# io-board-f-d.net
KiCad netlist of a schematic drawn in EAGLE
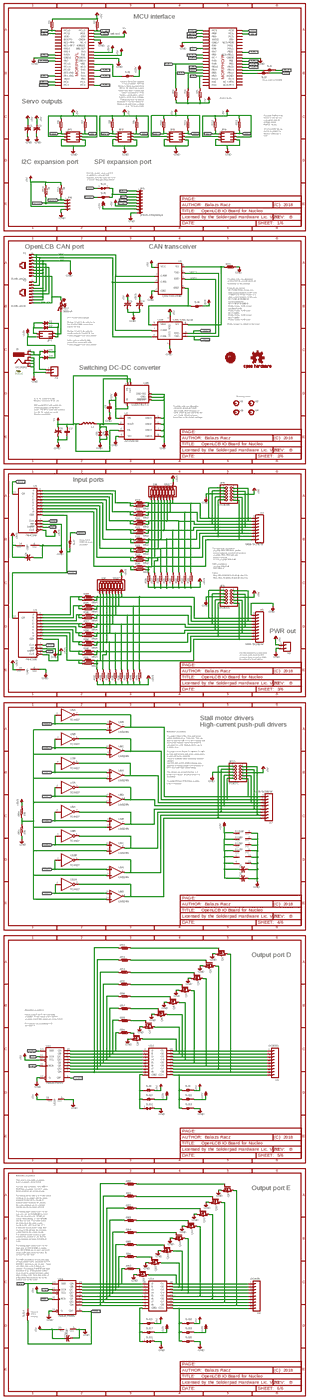
[diagram p0: schematic, sheet 1, overview]
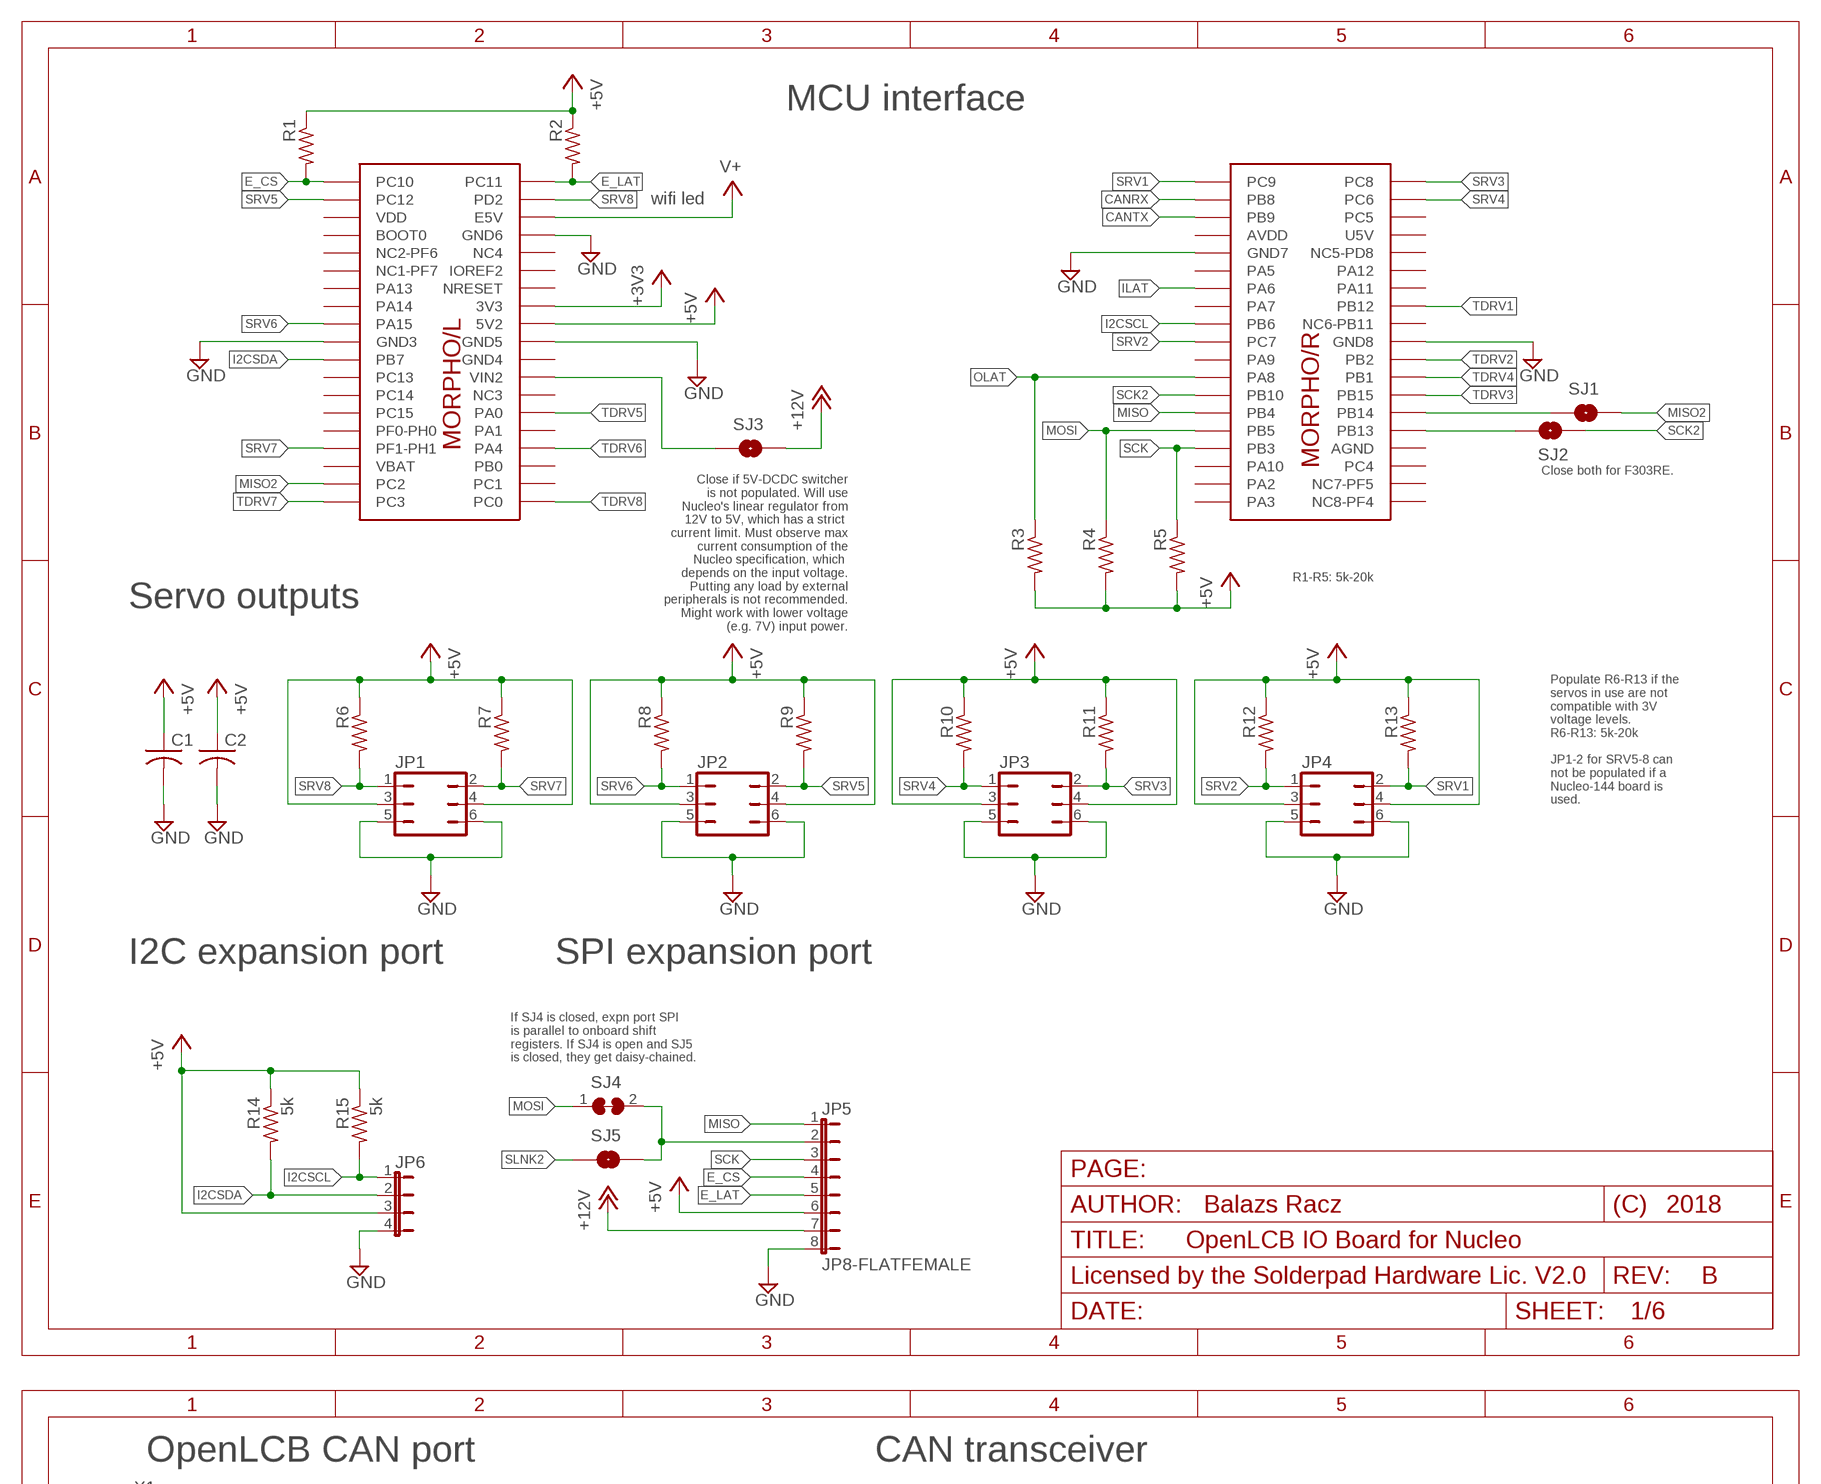
[diagram p1: schematic, sheet 1, part 1 of 4]
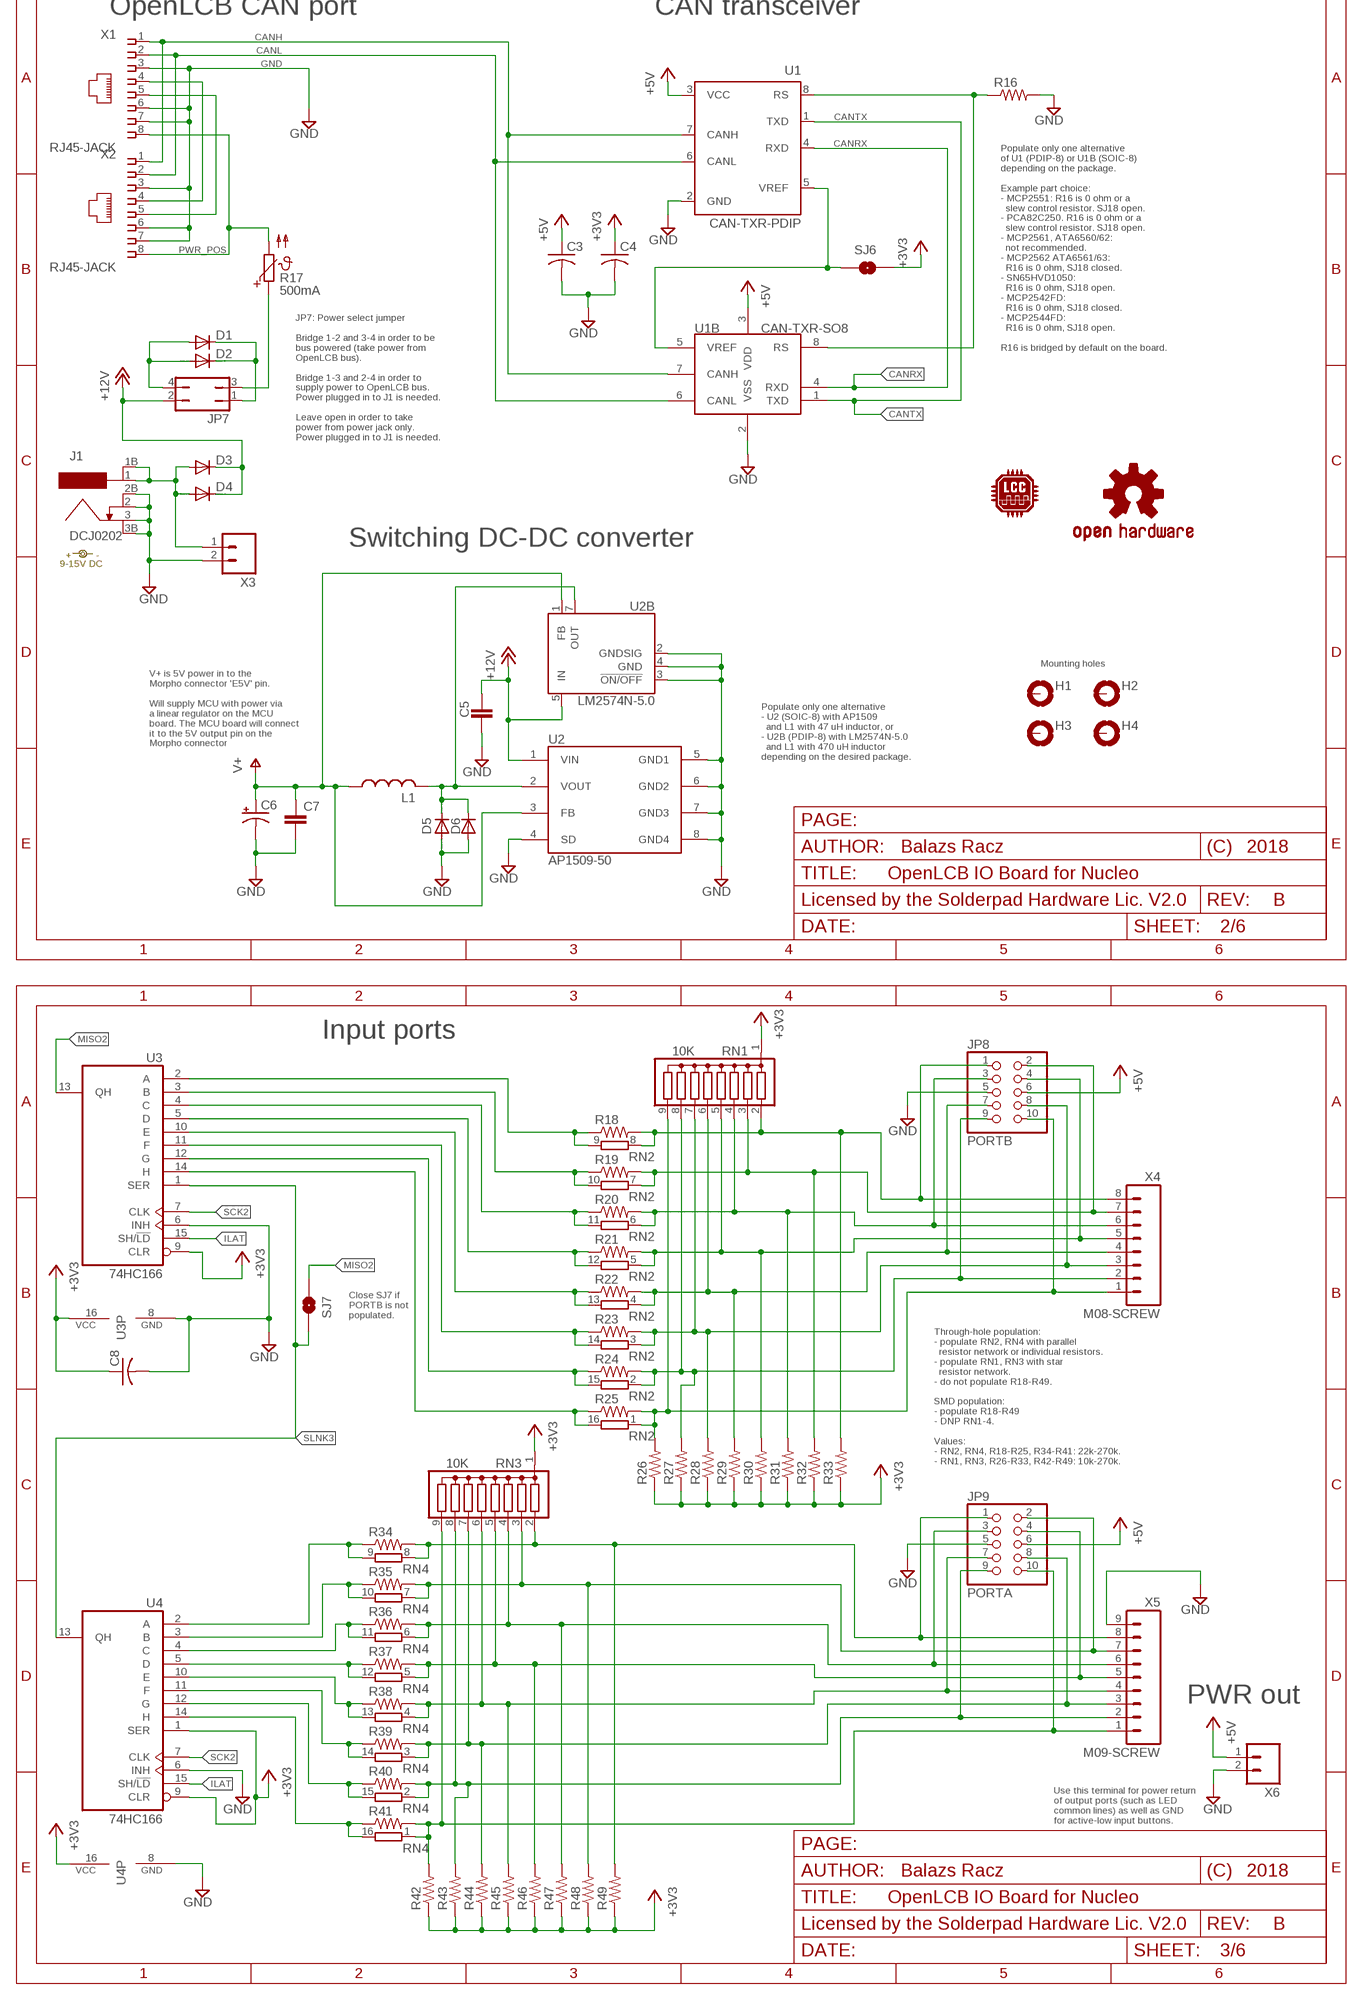
[diagram p2: schematic, sheet 1, part 2 of 4]
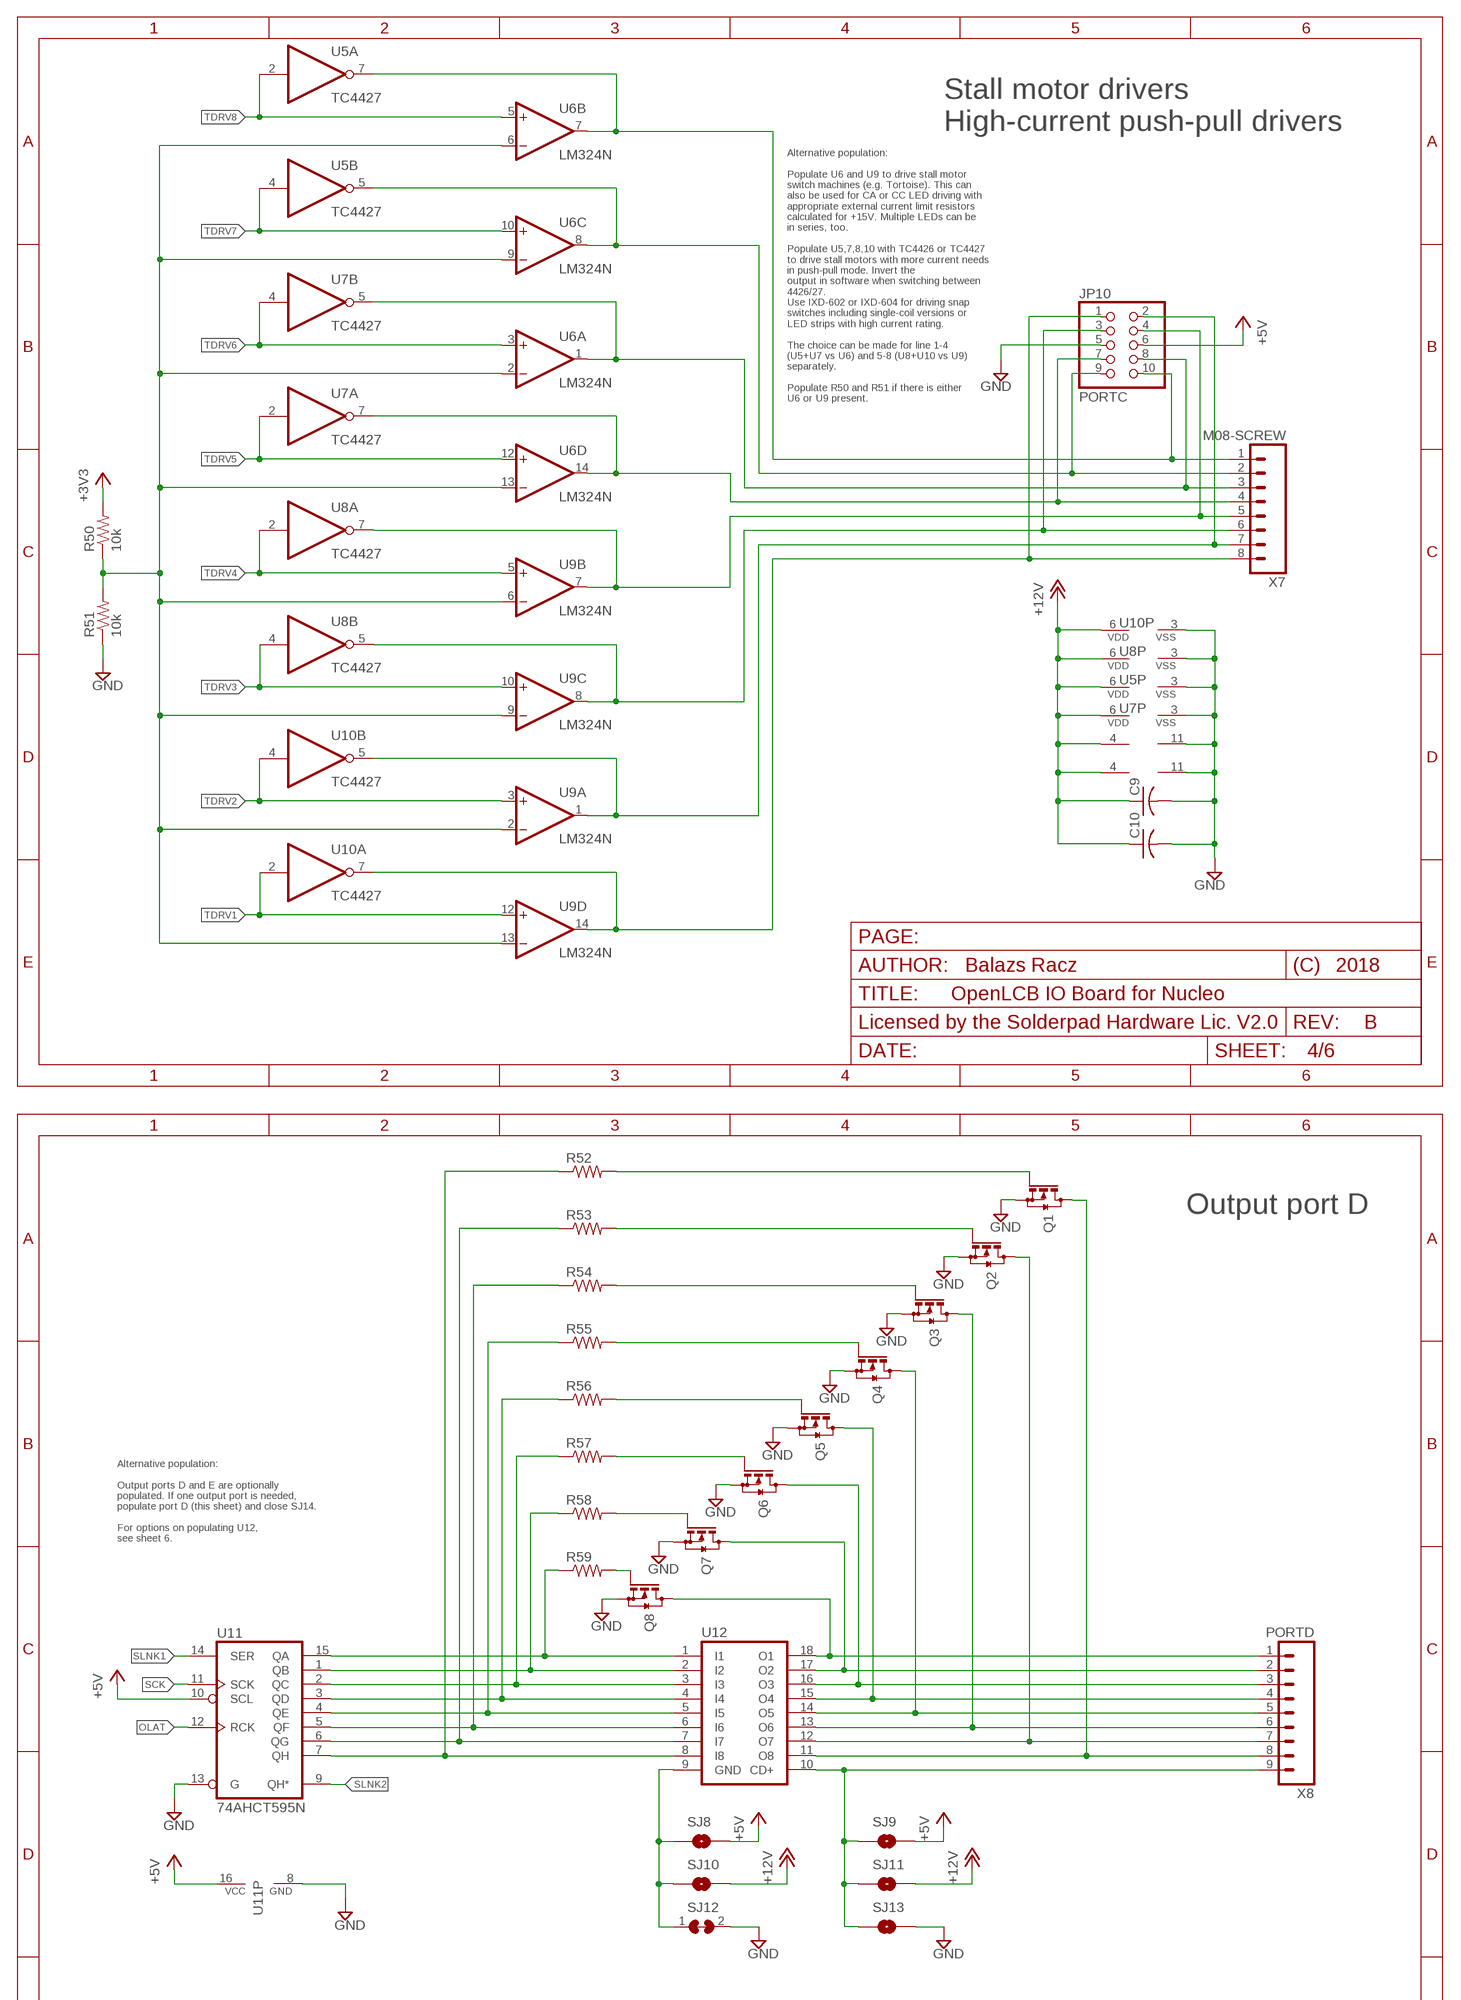
[diagram p3: schematic, sheet 1, part 3 of 4]
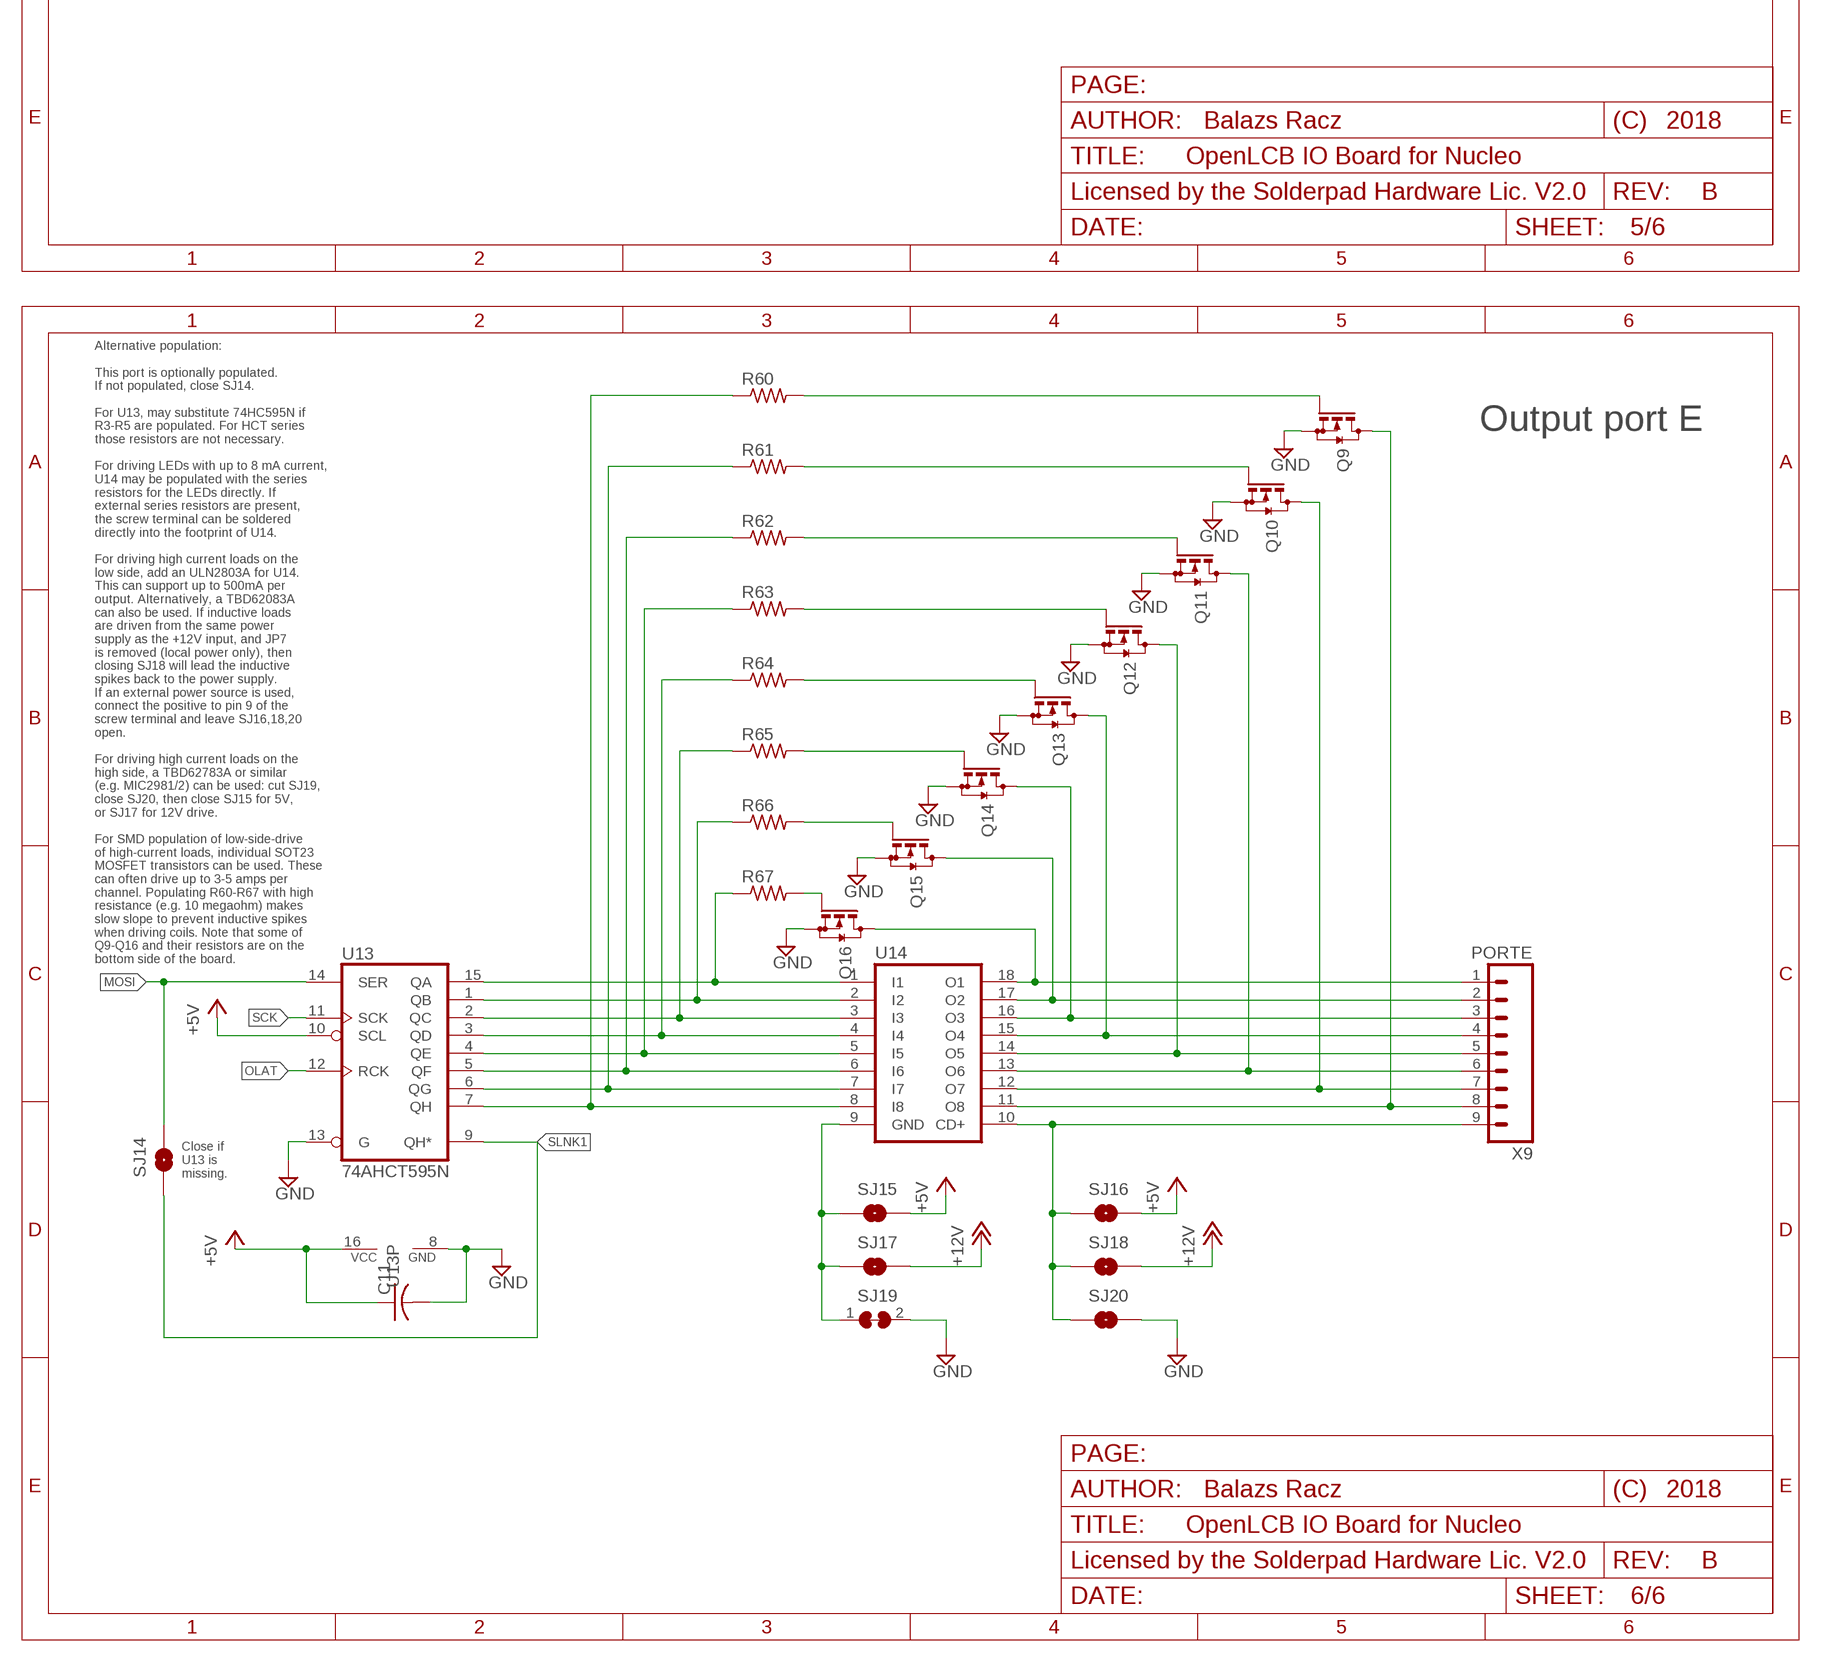
[diagram p4: schematic, sheet 1, part 4 of 4]

(export (version "E")
  (design (tool "Eeschema 10.0.6"))
  (components
    (comp (ref "C1")
      (value "C-USC1206")
      (footprint "eagle-import:C1206")
      (libsource (lib "eagle-import") (part "C-USC1206"))
    )
    (comp (ref "C2")
      (value "C-USC1206")
      (footprint "eagle-import:C1206")
      (libsource (lib "eagle-import") (part "C-USC1206"))
    )
    (comp (ref "C3")
      (value "C-USC0805")
      (footprint "eagle-import:C0805")
      (libsource (lib "eagle-import") (part "C-USC0805"))
    )
    (comp (ref "C4")
      (value "C-USC0805")
      (footprint "eagle-import:C0805")
      (libsource (lib "eagle-import") (part "C-USC0805"))
    )
    (comp (ref "C5")
      (value "C-EUC1206")
      (footprint "eagle-import:C1206")
      (libsource (lib "eagle-import") (part "C-EUC1206"))
    )
    (comp (ref "C6")
      (value "CPOL-USE2.5-5")
      (footprint "eagle-import:E2,5-5")
      (libsource (lib "eagle-import") (part "CPOL-USE2.5-5"))
    )
    (comp (ref "C7")
      (value "C-EUC1206")
      (footprint "eagle-import:C1206")
      (libsource (lib "eagle-import") (part "C-EUC1206"))
    )
    (comp (ref "C8")
      (value "C-USC0805")
      (footprint "eagle-import:C0805")
      (libsource (lib "eagle-import") (part "C-USC0805"))
    )
    (comp (ref "C9")
      (value "C-USC1206")
      (footprint "eagle-import:C1206")
      (libsource (lib "eagle-import") (part "C-USC1206"))
    )
    (comp (ref "C10")
      (value "C-USC1206")
      (footprint "eagle-import:C1206")
      (libsource (lib "eagle-import") (part "C-USC1206"))
    )
    (comp (ref "C11")
      (value "C-USC0805")
      (footprint "eagle-import:C0805")
      (libsource (lib "eagle-import") (part "C-USC0805"))
    )
    (comp (ref "D1")
      (value "DIODEDO-214AA-NODOC")
      (footprint "eagle-import:DO214AA-NODOC")
      (libsource (lib "eagle-import") (part "DIODEDO-214AA-NODOC"))
    )
    (comp (ref "D2")
      (value "DIODE-DO41-7.6")
      (footprint "eagle-import:DO41-7.6")
      (libsource (lib "eagle-import") (part "DIODE-DO41-7.6"))
    )
    (comp (ref "D3")
      (value "DIODEDO-214AA-NODOC")
      (footprint "eagle-import:DO214AA-NODOC")
      (libsource (lib "eagle-import") (part "DIODEDO-214AA-NODOC"))
    )
    (comp (ref "D4")
      (value "DIODE-DO41-7.6")
      (footprint "eagle-import:DO41-7.6")
      (libsource (lib "eagle-import") (part "DIODE-DO41-7.6"))
    )
    (comp (ref "D5")
      (value "DIODE-DO41-7.6")
      (footprint "eagle-import:DO41-7.6")
      (libsource (lib "eagle-import") (part "DIODE-DO41-7.6"))
    )
    (comp (ref "D6")
      (value "DIODEDO-214AA-NODOC")
      (footprint "eagle-import:DO214AA-NODOC")
      (libsource (lib "eagle-import") (part "DIODEDO-214AA-NODOC"))
    )
    (comp (ref "G1")
      (value "NUCLEO_64_GENERIC")
      (footprint "eagle-import:NUCLEO_BRD_BASE64")
      (libsource (lib "eagle-import") (part "NUCLEO_64_GENERIC"))
    )
    (comp (ref "H1")
      (value "MOUNT-PAD-ROUND3.3")
      (footprint "eagle-import:3,3-PAD")
      (libsource (lib "eagle-import") (part "MOUNT-PAD-ROUND3.3"))
    )
    (comp (ref "H2")
      (value "MOUNT-PAD-ROUND3.3")
      (footprint "eagle-import:3,3-PAD")
      (libsource (lib "eagle-import") (part "MOUNT-PAD-ROUND3.3"))
    )
    (comp (ref "H3")
      (value "MOUNT-PAD-ROUND3.3")
      (footprint "eagle-import:3,3-PAD")
      (libsource (lib "eagle-import") (part "MOUNT-PAD-ROUND3.3"))
    )
    (comp (ref "H4")
      (value "MOUNT-PAD-ROUND3.3")
      (footprint "eagle-import:3,3-PAD")
      (libsource (lib "eagle-import") (part "MOUNT-PAD-ROUND3.3"))
    )
    (comp (ref "J1")
      (value "DCJ0202")
      (footprint "eagle-import:DCJ0202")
      (libsource (lib "eagle-import") (part "DCJ0202"))
    )
    (comp (ref "JP1")
      (value "JP3Q")
      (footprint "eagle-import:JP3Q")
      (libsource (lib "eagle-import") (part "JP3Q"))
    )
    (comp (ref "JP2")
      (value "JP3Q")
      (footprint "eagle-import:JP3Q")
      (libsource (lib "eagle-import") (part "JP3Q"))
    )
    (comp (ref "JP3")
      (value "JP3Q")
      (footprint "eagle-import:JP3Q")
      (libsource (lib "eagle-import") (part "JP3Q"))
    )
    (comp (ref "JP4")
      (value "JP3Q")
      (footprint "eagle-import:JP3Q")
      (libsource (lib "eagle-import") (part "JP3Q"))
    )
    (comp (ref "JP5")
      (value "JP8-FLATFEMALE")
      (footprint "eagle-import:JP8F-FEM")
      (libsource (lib "eagle-import") (part "JP8-FLATFEMALE"))
    )
    (comp (ref "JP6")
      (value "JP4-FLAT")
      (footprint "eagle-import:JP4F")
      (libsource (lib "eagle-import") (part "JP4-FLAT"))
    )
    (comp (ref "JP7")
      (value "JP2Q")
      (footprint "eagle-import:JP2Q")
      (libsource (lib "eagle-import") (part "JP2Q"))
    )
    (comp (ref "JP8")
      (value "PORTB")
      (footprint "eagle-import:CON10M")
      (libsource (lib "eagle-import") (part "PINHD-2X5CN"))
    )
    (comp (ref "JP9")
      (value "PORTA")
      (footprint "eagle-import:CON10M")
      (libsource (lib "eagle-import") (part "PINHD-2X5CN"))
    )
    (comp (ref "JP10")
      (value "PORTC")
      (footprint "eagle-import:CON10M")
      (libsource (lib "eagle-import") (part "PINHD-2X5CN"))
    )
    (comp (ref "L1")
      (value "L-US")
      (footprint "eagle-import:L5-8,5")
      (libsource (lib "eagle-import") (part "L-US"))
    )
    (comp (ref "LG1")
      (value "LCC_LOGO")
      (footprint "eagle-import:LCC_LOGO")
      (libsource (lib "eagle-import") (part "LCC_LOGO"))
    )
    (comp (ref "LOGO1")
      (value "DOC-OSHW-LOGOM")
      (footprint "eagle-import:OSHW-LOGO-M")
      (libsource (lib "eagle-import") (part "DOC-OSHW-LOGOM"))
    )
    (comp (ref "P1")
      (value "9-15V DC")
      (footprint "eagle-import:POWER_USAGE")
      (libsource (lib "eagle-import") (part "DOC-POWER_LABEL"))
    )
    (comp (ref "Q1")
      (value "BSS123")
      (footprint "eagle-import:SOT23")
      (libsource (lib "eagle-import") (part "BSS123"))
    )
    (comp (ref "Q2")
      (value "BSS123")
      (footprint "eagle-import:SOT23")
      (libsource (lib "eagle-import") (part "BSS123"))
    )
    (comp (ref "Q3")
      (value "BSS123")
      (footprint "eagle-import:SOT23")
      (libsource (lib "eagle-import") (part "BSS123"))
    )
    (comp (ref "Q4")
      (value "BSS123")
      (footprint "eagle-import:SOT23")
      (libsource (lib "eagle-import") (part "BSS123"))
    )
    (comp (ref "Q5")
      (value "BSS123")
      (footprint "eagle-import:SOT23")
      (libsource (lib "eagle-import") (part "BSS123"))
    )
    (comp (ref "Q6")
      (value "BSS123")
      (footprint "eagle-import:SOT23")
      (libsource (lib "eagle-import") (part "BSS123"))
    )
    (comp (ref "Q7")
      (value "BSS123")
      (footprint "eagle-import:SOT23")
      (libsource (lib "eagle-import") (part "BSS123"))
    )
    (comp (ref "Q8")
      (value "BSS123")
      (footprint "eagle-import:SOT23")
      (libsource (lib "eagle-import") (part "BSS123"))
    )
    (comp (ref "Q9")
      (value "BSS123")
      (footprint "eagle-import:SOT23")
      (libsource (lib "eagle-import") (part "BSS123"))
    )
    (comp (ref "Q10")
      (value "BSS123")
      (footprint "eagle-import:SOT23")
      (libsource (lib "eagle-import") (part "BSS123"))
    )
    (comp (ref "Q11")
      (value "BSS123")
      (footprint "eagle-import:SOT23")
      (libsource (lib "eagle-import") (part "BSS123"))
    )
    (comp (ref "Q12")
      (value "BSS123")
      (footprint "eagle-import:SOT23")
      (libsource (lib "eagle-import") (part "BSS123"))
    )
    (comp (ref "Q13")
      (value "BSS123")
      (footprint "eagle-import:SOT23")
      (libsource (lib "eagle-import") (part "BSS123"))
    )
    (comp (ref "Q14")
      (value "BSS123")
      (footprint "eagle-import:SOT23")
      (libsource (lib "eagle-import") (part "BSS123"))
    )
    (comp (ref "Q15")
      (value "BSS123")
      (footprint "eagle-import:SOT23")
      (libsource (lib "eagle-import") (part "BSS123"))
    )
    (comp (ref "Q16")
      (value "BSS123")
      (footprint "eagle-import:SOT23")
      (libsource (lib "eagle-import") (part "BSS123"))
    )
    (comp (ref "R1")
      (value "R-US_R0805")
      (footprint "eagle-import:R0805")
      (libsource (lib "eagle-import") (part "rcl_334_R-US_R0805"))
    )
    (comp (ref "R2")
      (value "R-US_R0805")
      (footprint "eagle-import:R0805")
      (libsource (lib "eagle-import") (part "rcl_334_R-US_R0805"))
    )
    (comp (ref "R3")
      (value "R-US_R0805")
      (footprint "eagle-import:R0805")
      (libsource (lib "eagle-import") (part "rcl_334_R-US_R0805"))
    )
    (comp (ref "R4")
      (value "R-US_R0805")
      (footprint "eagle-import:R0805")
      (libsource (lib "eagle-import") (part "rcl_334_R-US_R0805"))
    )
    (comp (ref "R5")
      (value "R-US_R0805")
      (footprint "eagle-import:R0805")
      (libsource (lib "eagle-import") (part "rcl_334_R-US_R0805"))
    )
    (comp (ref "R6")
      (value "R-US_R0805")
      (footprint "eagle-import:R0805")
      (libsource (lib "eagle-import") (part "rcl_334_R-US_R0805"))
    )
    (comp (ref "R7")
      (value "R-US_R0805")
      (footprint "eagle-import:R0805")
      (libsource (lib "eagle-import") (part "rcl_334_R-US_R0805"))
    )
    (comp (ref "R8")
      (value "R-US_R0805")
      (footprint "eagle-import:R0805")
      (libsource (lib "eagle-import") (part "rcl_334_R-US_R0805"))
    )
    (comp (ref "R9")
      (value "R-US_R0805")
      (footprint "eagle-import:R0805")
      (libsource (lib "eagle-import") (part "rcl_334_R-US_R0805"))
    )
    (comp (ref "R10")
      (value "R-US_R0805")
      (footprint "eagle-import:R0805")
      (libsource (lib "eagle-import") (part "rcl_334_R-US_R0805"))
    )
    (comp (ref "R11")
      (value "R-US_R0805")
      (footprint "eagle-import:R0805")
      (libsource (lib "eagle-import") (part "rcl_334_R-US_R0805"))
    )
    (comp (ref "R12")
      (value "R-US_R0805")
      (footprint "eagle-import:R0805")
      (libsource (lib "eagle-import") (part "rcl_334_R-US_R0805"))
    )
    (comp (ref "R13")
      (value "R-US_R0805")
      (footprint "eagle-import:R0805")
      (libsource (lib "eagle-import") (part "rcl_334_R-US_R0805"))
    )
    (comp (ref "R14")
      (value "5k")
      (footprint "eagle-import:R0805")
      (libsource (lib "eagle-import") (part "rcl_334_R-US_R0805"))
    )
    (comp (ref "R15")
      (value "5k")
      (footprint "eagle-import:R0805")
      (libsource (lib "eagle-import") (part "rcl_334_R-US_R0805"))
    )
    (comp (ref "R16")
      (value "R-US_R0805")
      (footprint "eagle-import:R0805")
      (libsource (lib "eagle-import") (part "rcl_334_R-US_R0805"))
    )
    (comp (ref "R17")
      (value "500mA")
      (footprint "eagle-import:PTC1812")
      (libsource (lib "eagle-import") (part "PTC_1812"))
    )
    (comp (ref "R18")
      (value "R-US_R0603")
      (footprint "eagle-import:R0603")
      (libsource (lib "eagle-import") (part "rcl_334_R-US_R0603"))
    )
    (comp (ref "R19")
      (value "R-US_R0603")
      (footprint "eagle-import:R0603")
      (libsource (lib "eagle-import") (part "rcl_334_R-US_R0603"))
    )
    (comp (ref "R20")
      (value "R-US_R0603")
      (footprint "eagle-import:R0603")
      (libsource (lib "eagle-import") (part "rcl_334_R-US_R0603"))
    )
    (comp (ref "R21")
      (value "R-US_R0603")
      (footprint "eagle-import:R0603")
      (libsource (lib "eagle-import") (part "rcl_334_R-US_R0603"))
    )
    (comp (ref "R22")
      (value "R-US_R0603")
      (footprint "eagle-import:R0603")
      (libsource (lib "eagle-import") (part "rcl_334_R-US_R0603"))
    )
    (comp (ref "R23")
      (value "R-US_R0603")
      (footprint "eagle-import:R0603")
      (libsource (lib "eagle-import") (part "rcl_334_R-US_R0603"))
    )
    (comp (ref "R24")
      (value "R-US_R0603")
      (footprint "eagle-import:R0603")
      (libsource (lib "eagle-import") (part "rcl_334_R-US_R0603"))
    )
    (comp (ref "R25")
      (value "R-US_R0603")
      (footprint "eagle-import:R0603")
      (libsource (lib "eagle-import") (part "rcl_334_R-US_R0603"))
    )
    (comp (ref "R26")
      (value "R-US")
      (footprint "eagle-import:R0603")
      (libsource (lib "eagle-import") (part "R-US"))
    )
    (comp (ref "R27")
      (value "R-US")
      (footprint "eagle-import:R0603")
      (libsource (lib "eagle-import") (part "R-US"))
    )
    (comp (ref "R28")
      (value "R-US")
      (footprint "eagle-import:R0603")
      (libsource (lib "eagle-import") (part "R-US"))
    )
    (comp (ref "R29")
      (value "R-US")
      (footprint "eagle-import:R0603")
      (libsource (lib "eagle-import") (part "R-US"))
    )
    (comp (ref "R30")
      (value "R-US")
      (footprint "eagle-import:R0603")
      (libsource (lib "eagle-import") (part "R-US"))
    )
    (comp (ref "R31")
      (value "R-US")
      (footprint "eagle-import:R0603")
      (libsource (lib "eagle-import") (part "R-US"))
    )
    (comp (ref "R32")
      (value "R-US")
      (footprint "eagle-import:R0603")
      (libsource (lib "eagle-import") (part "R-US"))
    )
    (comp (ref "R33")
      (value "R-US")
      (footprint "eagle-import:R0603")
      (libsource (lib "eagle-import") (part "R-US"))
    )
    (comp (ref "R34")
      (value "R-US_R0603")
      (footprint "eagle-import:R0603")
      (libsource (lib "eagle-import") (part "rcl_334_R-US_R0603"))
    )
    (comp (ref "R35")
      (value "R-US_R0603")
      (footprint "eagle-import:R0603")
      (libsource (lib "eagle-import") (part "rcl_334_R-US_R0603"))
    )
    (comp (ref "R36")
      (value "R-US_R0603")
      (footprint "eagle-import:R0603")
      (libsource (lib "eagle-import") (part "rcl_334_R-US_R0603"))
    )
    (comp (ref "R37")
      (value "R-US_R0603")
      (footprint "eagle-import:R0603")
      (libsource (lib "eagle-import") (part "rcl_334_R-US_R0603"))
    )
    (comp (ref "R38")
      (value "R-US_R0603")
      (footprint "eagle-import:R0603")
      (libsource (lib "eagle-import") (part "rcl_334_R-US_R0603"))
    )
    (comp (ref "R39")
      (value "R-US_R0603")
      (footprint "eagle-import:R0603")
      (libsource (lib "eagle-import") (part "rcl_334_R-US_R0603"))
    )
    (comp (ref "R40")
      (value "R-US_R0603")
      (footprint "eagle-import:R0603")
      (libsource (lib "eagle-import") (part "rcl_334_R-US_R0603"))
    )
    (comp (ref "R41")
      (value "R-US_R0603")
      (footprint "eagle-import:R0603")
      (libsource (lib "eagle-import") (part "rcl_334_R-US_R0603"))
    )
    (comp (ref "R42")
      (value "R-US")
      (footprint "eagle-import:R0603")
      (libsource (lib "eagle-import") (part "R-US"))
    )
    (comp (ref "R43")
      (value "R-US")
      (footprint "eagle-import:R0603")
      (libsource (lib "eagle-import") (part "R-US"))
    )
    (comp (ref "R44")
      (value "R-US")
      (footprint "eagle-import:R0603")
      (libsource (lib "eagle-import") (part "R-US"))
    )
    (comp (ref "R45")
      (value "R-US")
      (footprint "eagle-import:R0603")
      (libsource (lib "eagle-import") (part "R-US"))
    )
    (comp (ref "R46")
      (value "R-US")
      (footprint "eagle-import:R0603")
      (libsource (lib "eagle-import") (part "R-US"))
    )
    (comp (ref "R47")
      (value "R-US")
      (footprint "eagle-import:R0603")
      (libsource (lib "eagle-import") (part "R-US"))
    )
    (comp (ref "R48")
      (value "R-US")
      (footprint "eagle-import:R0603")
      (libsource (lib "eagle-import") (part "R-US"))
    )
    (comp (ref "R49")
      (value "R-US")
      (footprint "eagle-import:R0603")
      (libsource (lib "eagle-import") (part "R-US"))
    )
    (comp (ref "R50")
      (value "10k")
      (footprint "eagle-import:R0805")
      (libsource (lib "eagle-import") (part "R-US_R0805"))
    )
    (comp (ref "R51")
      (value "10k")
      (footprint "eagle-import:R0805")
      (libsource (lib "eagle-import") (part "R-US_R0805"))
    )
    (comp (ref "R52")
      (value "R-US_R0603")
      (footprint "eagle-import:R0603")
      (libsource (lib "eagle-import") (part "R-US_R0603"))
    )
    (comp (ref "R53")
      (value "R-US_R0603")
      (footprint "eagle-import:R0603")
      (libsource (lib "eagle-import") (part "R-US_R0603"))
    )
    (comp (ref "R54")
      (value "R-US_R0603")
      (footprint "eagle-import:R0603")
      (libsource (lib "eagle-import") (part "R-US_R0603"))
    )
    (comp (ref "R55")
      (value "R-US_R0603")
      (footprint "eagle-import:R0603")
      (libsource (lib "eagle-import") (part "R-US_R0603"))
    )
    (comp (ref "R56")
      (value "R-US_R0603")
      (footprint "eagle-import:R0603")
      (libsource (lib "eagle-import") (part "R-US_R0603"))
    )
    (comp (ref "R57")
      (value "R-US_R0603")
      (footprint "eagle-import:R0603")
      (libsource (lib "eagle-import") (part "R-US_R0603"))
    )
    (comp (ref "R58")
      (value "R-US_R0603")
      (footprint "eagle-import:R0603")
      (libsource (lib "eagle-import") (part "R-US_R0603"))
    )
    (comp (ref "R59")
      (value "R-US_R0603")
      (footprint "eagle-import:R0603")
      (libsource (lib "eagle-import") (part "R-US_R0603"))
    )
    (comp (ref "R60")
      (value "R-US_R0603")
      (footprint "eagle-import:R0603")
      (libsource (lib "eagle-import") (part "R-US_R0603"))
    )
    (comp (ref "R61")
      (value "R-US_R0603")
      (footprint "eagle-import:R0603")
      (libsource (lib "eagle-import") (part "R-US_R0603"))
    )
    (comp (ref "R62")
      (value "R-US_R0603")
      (footprint "eagle-import:R0603")
      (libsource (lib "eagle-import") (part "R-US_R0603"))
    )
    (comp (ref "R63")
      (value "R-US_R0603")
      (footprint "eagle-import:R0603")
      (libsource (lib "eagle-import") (part "R-US_R0603"))
    )
    (comp (ref "R64")
      (value "R-US_R0603")
      (footprint "eagle-import:R0603")
      (libsource (lib "eagle-import") (part "R-US_R0603"))
    )
    (comp (ref "R65")
      (value "R-US_R0603")
      (footprint "eagle-import:R0603")
      (libsource (lib "eagle-import") (part "R-US_R0603"))
    )
    (comp (ref "R66")
      (value "R-US_R0603")
      (footprint "eagle-import:R0603")
      (libsource (lib "eagle-import") (part "R-US_R0603"))
    )
    (comp (ref "R67")
      (value "R-US_R0603")
      (footprint "eagle-import:R0603")
      (libsource (lib "eagle-import") (part "R-US_R0603"))
    )
    (comp (ref "RN1")
      (value "10K")
      (footprint "eagle-import:SIL9")
      (libsource (lib "eagle-import") (part "G08R"))
    )
    (comp (ref "RN2")
      (value "8R-P")
      (footprint "eagle-import:DIL16")
      (libsource (lib "eagle-import") (part "8R-P"))
    )
    (comp (ref "RN3")
      (value "10K")
      (footprint "eagle-import:SIL9")
      (libsource (lib "eagle-import") (part "G08R"))
    )
    (comp (ref "RN4")
      (value "8R-P")
      (footprint "eagle-import:DIL16")
      (libsource (lib "eagle-import") (part "8R-P"))
    )
    (comp (ref "SJ1")
      (value "SJRND2")
      (footprint "eagle-import:SJ_RND2")
      (libsource (lib "eagle-import") (part "SJRND2"))
    )
    (comp (ref "SJ2")
      (value "SJRND2")
      (footprint "eagle-import:SJ_RND2")
      (libsource (lib "eagle-import") (part "SJRND2"))
    )
    (comp (ref "SJ3")
      (value "SJRND2")
      (footprint "eagle-import:SJ_RND2")
      (libsource (lib "eagle-import") (part "SJRND2"))
    )
    (comp (ref "SJ4")
      (value "SJ-C")
      (footprint "eagle-import:SJW-C")
      (libsource (lib "eagle-import") (part "SJ-C"))
    )
    (comp (ref "SJ5")
      (value "SJRND2")
      (footprint "eagle-import:SJ_RND2")
      (libsource (lib "eagle-import") (part "SJRND2"))
    )
    (comp (ref "SJ6")
      (value "SJRND2")
      (footprint "eagle-import:SJ_RND2")
      (libsource (lib "eagle-import") (part "SJRND2"))
    )
    (comp (ref "SJ7")
      (value "SJRND2")
      (footprint "eagle-import:SJ_RND2")
      (libsource (lib "eagle-import") (part "SJRND2"))
    )
    (comp (ref "SJ8")
      (value "SJRND2")
      (footprint "eagle-import:SJ_RND2")
      (libsource (lib "eagle-import") (part "SJRND2"))
    )
    (comp (ref "SJ9")
      (value "SJRND2")
      (footprint "eagle-import:SJ_RND2")
      (libsource (lib "eagle-import") (part "SJRND2"))
    )
    (comp (ref "SJ10")
      (value "SJRND2")
      (footprint "eagle-import:SJ_RND2")
      (libsource (lib "eagle-import") (part "SJRND2"))
    )
    (comp (ref "SJ11")
      (value "SJRND2")
      (footprint "eagle-import:SJ_RND2")
      (libsource (lib "eagle-import") (part "SJRND2"))
    )
    (comp (ref "SJ12")
      (value "SJ-C")
      (footprint "eagle-import:SJW-C")
      (libsource (lib "eagle-import") (part "SJ-C"))
    )
    (comp (ref "SJ13")
      (value "SJRND2")
      (footprint "eagle-import:SJ_RND2")
      (libsource (lib "eagle-import") (part "SJRND2"))
    )
    (comp (ref "SJ14")
      (value "SJRND2")
      (footprint "eagle-import:SJ_RND2")
      (libsource (lib "eagle-import") (part "SJRND2"))
    )
    (comp (ref "SJ15")
      (value "SJRND2")
      (footprint "eagle-import:SJ_RND2")
      (libsource (lib "eagle-import") (part "SJRND2"))
    )
    (comp (ref "SJ16")
      (value "SJRND2")
      (footprint "eagle-import:SJ_RND2")
      (libsource (lib "eagle-import") (part "SJRND2"))
    )
    (comp (ref "SJ17")
      (value "SJRND2")
      (footprint "eagle-import:SJ_RND2")
      (libsource (lib "eagle-import") (part "SJRND2"))
    )
    (comp (ref "SJ18")
      (value "SJRND2")
      (footprint "eagle-import:SJ_RND2")
      (libsource (lib "eagle-import") (part "SJRND2"))
    )
    (comp (ref "SJ19")
      (value "SJ-C")
      (footprint "eagle-import:SJW-C")
      (libsource (lib "eagle-import") (part "SJ-C"))
    )
    (comp (ref "SJ20")
      (value "SJRND2")
      (footprint "eagle-import:SJ_RND2")
      (libsource (lib "eagle-import") (part "SJRND2"))
    )
    (comp (ref "U1")
      (value "CAN-TXR-PDIP")
      (footprint "eagle-import:DIL08")
      (libsource (lib "eagle-import") (part "PCA82C250"))
    )
    (comp (ref "U1B")
      (value "CAN-TXR-SO8")
      (footprint "eagle-import:SO-08")
      (libsource (lib "eagle-import") (part "MCP2551-SN"))
    )
    (comp (ref "U2")
      (value "AP1509-50")
      (footprint "eagle-import:SO-08")
      (libsource (lib "eagle-import") (part "AP1509"))
    )
    (comp (ref "U2B")
      (value "LM2574N-5.0")
      (footprint "eagle-import:DIL08")
      (libsource (lib "eagle-import") (part "LM2574?-N5.0"))
    )
    (comp (ref "U3")
      (value "74HC166")
      (footprint "eagle-import:DIL16")
      (libsource (lib "eagle-import") (part "74166N"))
    )
    (comp (ref "U4")
      (value "74HC166")
      (footprint "eagle-import:DIL16")
      (libsource (lib "eagle-import") (part "74166N"))
    )
    (comp (ref "U5")
      (value "TC4427")
      (footprint "eagle-import:DIL08-LONG")
      (libsource (lib "eagle-import") (part "TC4426APDIP"))
    )
    (comp (ref "U6")
      (value "LM324N")
      (footprint "eagle-import:DIL14")
      (libsource (lib "eagle-import") (part "LM324N"))
    )
    (comp (ref "U7")
      (value "TC4427")
      (footprint "eagle-import:DIL08-LONG")
      (libsource (lib "eagle-import") (part "TC4426APDIP"))
    )
    (comp (ref "U8")
      (value "TC4427")
      (footprint "eagle-import:DIL08-LONG")
      (libsource (lib "eagle-import") (part "TC4426APDIP"))
    )
    (comp (ref "U9")
      (value "LM324N")
      (footprint "eagle-import:DIL14")
      (libsource (lib "eagle-import") (part "LM324N"))
    )
    (comp (ref "U10")
      (value "TC4427")
      (footprint "eagle-import:DIL08-LONG")
      (libsource (lib "eagle-import") (part "TC4426APDIP"))
    )
    (comp (ref "U11")
      (value "74AHCT595N")
      (footprint "eagle-import:DIL16")
      (libsource (lib "eagle-import") (part "74595NHCT"))
    )
    (comp (ref "U12")
      (value "ULN2803A")
      (footprint "eagle-import:DIL18-THIN")
      (libsource (lib "eagle-import") (part "ULN2803A"))
    )
    (comp (ref "U13")
      (value "74AHCT595N")
      (footprint "eagle-import:DIL16")
      (libsource (lib "eagle-import") (part "74595NHCT"))
    )
    (comp (ref "U14")
      (value "ULN2803A")
      (footprint "eagle-import:DIL18-THIN")
      (libsource (lib "eagle-import") (part "ULN2803A"))
    )
    (comp (ref "X1")
      (value "RJ45-JACK")
      (footprint "eagle-import:RJ45-PULSE-E5J88")
      (libsource (lib "eagle-import") (part "RJ45-JACKRJ45-PULSE-E5J00"))
    )
    (comp (ref "X2")
      (value "RJ45-JACK")
      (footprint "eagle-import:RJ45-PULSE-E5J88")
      (libsource (lib "eagle-import") (part "RJ45-JACKRJ45-PULSE-E5J00"))
    )
    (comp (ref "X3")
      (value "CONNECTOR-M023.5MM-LOCK")
      (footprint "eagle-import:SCREWTERMINAL-3.5MM-2_LOCK")
      (libsource (lib "eagle-import") (part "CONNECTOR-M023.5MM-LOCK"))
    )
    (comp (ref "X4")
      (value "M08-SCREW")
      (footprint "eagle-import:1X08_TERMINAL")
      (libsource (lib "eagle-import") (part "M08-SCREW"))
    )
    (comp (ref "X5")
      (value "M09-SCREW")
      (footprint "eagle-import:1X09_TERMINAL")
      (libsource (lib "eagle-import") (part "M09-SCREW"))
    )
    (comp (ref "X6")
      (value "CONNECTOR-M023.5MM-LOCK")
      (footprint "eagle-import:SCREWTERMINAL-3.5MM-2_LOCK")
      (libsource (lib "eagle-import") (part "CONNECTOR-M023.5MM-LOCK"))
    )
    (comp (ref "X7")
      (value "M08-SCREW")
      (footprint "eagle-import:1X08_TERMINAL")
      (libsource (lib "eagle-import") (part "M08-SCREW"))
    )
    (comp (ref "X8")
      (value "PORTD")
      (footprint "eagle-import:1X09_TERMINAL")
      (libsource (lib "eagle-import") (part "M09-SCREW"))
    )
    (comp (ref "X9")
      (value "PORTE")
      (footprint "eagle-import:1X09_TERMINAL")
      (libsource (lib "eagle-import") (part "M09-SCREW"))
    )
  )
  (nets
    (net (code "1") (name "+3V3") (class "Default")
      (node (ref "C4") (pin "1") (pinfunction "1_1") (pintype "passive"))
      (node (ref "C8") (pin "1") (pinfunction "1_1") (pintype "passive"))
      (node (ref "G1") (pin "3V3") (pinfunction "3V3_3V3") (pintype "power_in"))
      (node (ref "R26") (pin "1") (pinfunction "1_1") (pintype "passive"))
      (node (ref "R27") (pin "1") (pinfunction "1_1") (pintype "passive"))
      (node (ref "R28") (pin "1") (pinfunction "1_1") (pintype "passive"))
      (node (ref "R29") (pin "1") (pinfunction "1_1") (pintype "passive"))
      (node (ref "R30") (pin "1") (pinfunction "1_1") (pintype "passive"))
      (node (ref "R31") (pin "1") (pinfunction "1_1") (pintype "passive"))
      (node (ref "R32") (pin "1") (pinfunction "1_1") (pintype "passive"))
      (node (ref "R33") (pin "1") (pinfunction "1_1") (pintype "passive"))
      (node (ref "R42") (pin "1") (pinfunction "1_1") (pintype "passive"))
      (node (ref "R43") (pin "1") (pinfunction "1_1") (pintype "passive"))
      (node (ref "R44") (pin "1") (pinfunction "1_1") (pintype "passive"))
      (node (ref "R45") (pin "1") (pinfunction "1_1") (pintype "passive"))
      (node (ref "R46") (pin "1") (pinfunction "1_1") (pintype "passive"))
      (node (ref "R47") (pin "1") (pinfunction "1_1") (pintype "passive"))
      (node (ref "R48") (pin "1") (pinfunction "1_1") (pintype "passive"))
      (node (ref "R49") (pin "1") (pinfunction "1_1") (pintype "passive"))
      (node (ref "R50") (pin "2") (pinfunction "2_2") (pintype "passive"))
      (node (ref "RN1") (pin "1") (pinfunction "1_1") (pintype "passive"))
      (node (ref "RN3") (pin "1") (pinfunction "1_1") (pintype "passive"))
      (node (ref "SJ6") (pin "P$2") (pinfunction "2_P$2") (pintype "passive"))
      (node (ref "U3") (pin "16") (pinfunction "VCC_16") (pintype "power_in"))
      (node (ref "U3") (pin "9") (pinfunction "CLR_9") (pintype "input"))
      (node (ref "U4") (pin "1") (pinfunction "SER_1") (pintype "input"))
      (node (ref "U4") (pin "16") (pinfunction "VCC_16") (pintype "power_in"))
      (node (ref "U4") (pin "9") (pinfunction "CLR_9") (pintype "input"))
    )
    (net (code "2") (name "+5V") (class "Default")
      (node (ref "C1") (pin "1") (pinfunction "1_1") (pintype "passive"))
      (node (ref "C11") (pin "1") (pinfunction "1_1") (pintype "passive"))
      (node (ref "C2") (pin "1") (pinfunction "1_1") (pintype "passive"))
      (node (ref "C3") (pin "1") (pinfunction "1_1") (pintype "passive"))
      (node (ref "G1") (pin "5V2") (pinfunction "5V2_5V2") (pintype "power_in"))
      (node (ref "JP1") (pin "3") (pinfunction "3_3") (pintype "passive"))
      (node (ref "JP1") (pin "4") (pinfunction "4_4") (pintype "passive"))
      (node (ref "JP10") (pin "6") (pinfunction "6_6") (pintype "passive"))
      (node (ref "JP2") (pin "3") (pinfunction "3_3") (pintype "passive"))
      (node (ref "JP2") (pin "4") (pinfunction "4_4") (pintype "passive"))
      (node (ref "JP3") (pin "3") (pinfunction "3_3") (pintype "passive"))
      (node (ref "JP3") (pin "4") (pinfunction "4_4") (pintype "passive"))
      (node (ref "JP4") (pin "3") (pinfunction "3_3") (pintype "passive"))
      (node (ref "JP4") (pin "4") (pinfunction "4_4") (pintype "passive"))
      (node (ref "JP5") (pin "6") (pinfunction "6_6") (pintype "passive"))
      (node (ref "JP6") (pin "3") (pinfunction "3_3") (pintype "passive"))
      (node (ref "JP8") (pin "6") (pinfunction "6_6") (pintype "passive"))
      (node (ref "JP9") (pin "6") (pinfunction "6_6") (pintype "passive"))
      (node (ref "R1") (pin "1") (pinfunction "1_1") (pintype "passive"))
      (node (ref "R10") (pin "1") (pinfunction "1_1") (pintype "passive"))
      (node (ref "R11") (pin "1") (pinfunction "1_1") (pintype "passive"))
      (node (ref "R12") (pin "1") (pinfunction "1_1") (pintype "passive"))
      (node (ref "R13") (pin "1") (pinfunction "1_1") (pintype "passive"))
      (node (ref "R14") (pin "1") (pinfunction "1_1") (pintype "passive"))
      (node (ref "R15") (pin "1") (pinfunction "1_1") (pintype "passive"))
      (node (ref "R2") (pin "1") (pinfunction "1_1") (pintype "passive"))
      (node (ref "R3") (pin "2") (pinfunction "2_2") (pintype "passive"))
      (node (ref "R4") (pin "2") (pinfunction "2_2") (pintype "passive"))
      (node (ref "R5") (pin "2") (pinfunction "2_2") (pintype "passive"))
      (node (ref "R6") (pin "1") (pinfunction "1_1") (pintype "passive"))
      (node (ref "R7") (pin "1") (pinfunction "1_1") (pintype "passive"))
      (node (ref "R8") (pin "1") (pinfunction "1_1") (pintype "passive"))
      (node (ref "R9") (pin "1") (pinfunction "1_1") (pintype "passive"))
      (node (ref "SJ15") (pin "P$2") (pinfunction "2_P$2") (pintype "passive"))
      (node (ref "SJ16") (pin "P$2") (pinfunction "2_P$2") (pintype "passive"))
      (node (ref "SJ8") (pin "P$2") (pinfunction "2_P$2") (pintype "passive"))
      (node (ref "SJ9") (pin "P$2") (pinfunction "2_P$2") (pintype "passive"))
      (node (ref "U1") (pin "3") (pinfunction "VCC_3") (pintype "power_in"))
      (node (ref "U11") (pin "10") (pinfunction "SCL_10") (pintype "input"))
      (node (ref "U11") (pin "16") (pinfunction "VCC_16") (pintype "power_in"))
      (node (ref "U13") (pin "10") (pinfunction "SCL_10") (pintype "input"))
      (node (ref "U13") (pin "16") (pinfunction "VCC_16") (pintype "power_in"))
      (node (ref "U1B") (pin "3") (pinfunction "VDD_3") (pintype "power_in"))
      (node (ref "X6") (pin "1") (pinfunction "1_1") (pintype "passive"))
    )
    (net (code "3") (name "+12V") (class "Default")
      (node (ref "C10") (pin "1") (pinfunction "1_1") (pintype "passive"))
      (node (ref "C5") (pin "1") (pinfunction "1_1") (pintype "passive"))
      (node (ref "C9") (pin "1") (pinfunction "1_1") (pintype "passive"))
      (node (ref "D3") (pin "C") (pinfunction "C_C") (pintype "passive"))
      (node (ref "D4") (pin "C") (pinfunction "C_C") (pintype "passive"))
      (node (ref "JP5") (pin "7") (pinfunction "7_7") (pintype "passive"))
      (node (ref "JP7") (pin "2") (pinfunction "2_2") (pintype "passive"))
      (node (ref "SJ10") (pin "P$2") (pinfunction "2_P$2") (pintype "passive"))
      (node (ref "SJ11") (pin "P$2") (pinfunction "2_P$2") (pintype "passive"))
      (node (ref "SJ17") (pin "P$2") (pinfunction "2_P$2") (pintype "passive"))
      (node (ref "SJ18") (pin "P$2") (pinfunction "2_P$2") (pintype "passive"))
      (node (ref "SJ3") (pin "P$2") (pinfunction "2_P$2") (pintype "passive"))
      (node (ref "U10") (pin "6") (pinfunction "VDD_6") (pintype "power_in"))
      (node (ref "U2") (pin "1") (pinfunction "VIN_1") (pintype "bidirectional"))
      (node (ref "U2B") (pin "5") (pinfunction "IN_5") (pintype "input"))
      (node (ref "U5") (pin "6") (pinfunction "VDD_6") (pintype "power_in"))
      (node (ref "U6") (pin "4") (pinfunction "V+_4") (pintype "power_in"))
      (node (ref "U7") (pin "6") (pinfunction "VDD_6") (pintype "power_in"))
      (node (ref "U8") (pin "6") (pinfunction "VDD_6") (pintype "power_in"))
      (node (ref "U9") (pin "4") (pinfunction "V+_4") (pintype "power_in"))
    )
    (net (code "4") (name "/AGND") (class "Default")
      (node (ref "G1") (pin "AGND") (pinfunction "AGND_AGND") (pintype "power_in"))
    )
    (net (code "5") (name "/AVDD") (class "Default")
      (node (ref "G1") (pin "AVDD") (pinfunction "AVDD_AVDD") (pintype "power_in"))
    )
    (net (code "6") (name "/CANH") (class "Default")
      (node (ref "U1") (pin "7") (pinfunction "CANH_7") (pintype "bidirectional"))
      (node (ref "U1B") (pin "7") (pinfunction "CANH_7") (pintype "bidirectional"))
      (node (ref "X1") (pin "1") (pinfunction "1_1") (pintype "passive"))
      (node (ref "X2") (pin "1") (pinfunction "1_1") (pintype "passive"))
    )
    (net (code "7") (name "/CANL") (class "Default")
      (node (ref "U1") (pin "6") (pinfunction "CANL_6") (pintype "bidirectional"))
      (node (ref "U1B") (pin "6") (pinfunction "CANL_6") (pintype "bidirectional"))
      (node (ref "X1") (pin "2") (pinfunction "2_2") (pintype "passive"))
      (node (ref "X2") (pin "2") (pinfunction "2_2") (pintype "passive"))
    )
    (net (code "8") (name "/GND4") (class "Default")
      (node (ref "G1") (pin "GND4") (pinfunction "GND4_GND4") (pintype "power_in"))
    )
    (net (code "9") (name "/PWR_POS") (class "Default")
      (node (ref "R17") (pin "2") (pinfunction "2_2") (pintype "passive"))
      (node (ref "X1") (pin "8") (pinfunction "8_8") (pintype "passive"))
      (node (ref "X2") (pin "8") (pinfunction "8_8") (pintype "passive"))
    )
    (net (code "10") (name "/U5V") (class "Default")
      (node (ref "G1") (pin "U5V") (pinfunction "U5V_U5V") (pintype "power_in"))
    )
    (net (code "11") (name "/VBAT") (class "Default")
      (node (ref "G1") (pin "VBAT") (pinfunction "VBAT_VBAT") (pintype "power_in"))
    )
    (net (code "12") (name "/VDD") (class "Default")
      (node (ref "G1") (pin "VDD") (pinfunction "VDD_VDD") (pintype "power_in"))
    )
    (net (code "13") (name "CANRX") (class "Default")
      (node (ref "G1") (pin "PB8") (pinfunction "PB8_PB8") (pintype "bidirectional"))
      (node (ref "U1") (pin "4") (pinfunction "RXD_4") (pintype "output"))
      (node (ref "U1B") (pin "4") (pinfunction "RXD_4") (pintype "bidirectional"))
    )
    (net (code "14") (name "CANTX") (class "Default")
      (node (ref "G1") (pin "PB9") (pinfunction "PB9_PB9") (pintype "bidirectional"))
      (node (ref "U1") (pin "1") (pinfunction "TXD_1") (pintype "input"))
      (node (ref "U1B") (pin "1") (pinfunction "TXD_1") (pintype "bidirectional"))
    )
    (net (code "15") (name "E_CS") (class "Default")
      (node (ref "G1") (pin "PC10") (pinfunction "PC10_PC10") (pintype "bidirectional"))
      (node (ref "JP5") (pin "4") (pinfunction "4_4") (pintype "passive"))
      (node (ref "R1") (pin "2") (pinfunction "2_2") (pintype "passive"))
    )
    (net (code "16") (name "E_LAT") (class "Default")
      (node (ref "G1") (pin "PC11") (pinfunction "PC11_PC11") (pintype "bidirectional"))
      (node (ref "JP5") (pin "5") (pinfunction "5_5") (pintype "passive"))
      (node (ref "R2") (pin "2") (pinfunction "2_2") (pintype "passive"))
    )
    (net (code "17") (name "GND") (class "Default")
      (node (ref "C1") (pin "2") (pinfunction "2_2") (pintype "passive"))
      (node (ref "C10") (pin "2") (pinfunction "2_2") (pintype "passive"))
      (node (ref "C11") (pin "2") (pinfunction "2_2") (pintype "passive"))
      (node (ref "C2") (pin "2") (pinfunction "2_2") (pintype "passive"))
      (node (ref "C3") (pin "2") (pinfunction "2_2") (pintype "passive"))
      (node (ref "C4") (pin "2") (pinfunction "2_2") (pintype "passive"))
      (node (ref "C5") (pin "2") (pinfunction "2_2") (pintype "passive"))
      (node (ref "C6") (pin "-") (pinfunction "-_-") (pintype "passive"))
      (node (ref "C7") (pin "2") (pinfunction "2_2") (pintype "passive"))
      (node (ref "C8") (pin "2") (pinfunction "2_2") (pintype "passive"))
      (node (ref "C9") (pin "2") (pinfunction "2_2") (pintype "passive"))
      (node (ref "D5") (pin "A") (pinfunction "A_A") (pintype "passive"))
      (node (ref "D6") (pin "A") (pinfunction "A_A") (pintype "passive"))
      (node (ref "G1") (pin "GND3") (pinfunction "GND3_GND3") (pintype "power_in"))
      (node (ref "G1") (pin "GND5") (pinfunction "GND5_GND5") (pintype "power_in"))
      (node (ref "G1") (pin "GND6") (pinfunction "GND6_GND6") (pintype "power_in"))
      (node (ref "G1") (pin "GND7") (pinfunction "GND7_GND7") (pintype "power_in"))
      (node (ref "G1") (pin "GND8") (pinfunction "GND8_GND8") (pintype "power_in"))
      (node (ref "J1") (pin "2") (pinfunction "2_2") (pintype "passive"))
      (node (ref "J1") (pin "2B") (pinfunction "2B_2B") (pintype "passive"))
      (node (ref "J1") (pin "3") (pinfunction "3_3") (pintype "passive"))
      (node (ref "J1") (pin "3B") (pinfunction "3B_3B") (pintype "passive"))
      (node (ref "JP1") (pin "5") (pinfunction "5_5") (pintype "passive"))
      (node (ref "JP1") (pin "6") (pinfunction "6_6") (pintype "passive"))
      (node (ref "JP10") (pin "5") (pinfunction "5_5") (pintype "passive"))
      (node (ref "JP2") (pin "5") (pinfunction "5_5") (pintype "passive"))
      (node (ref "JP2") (pin "6") (pinfunction "6_6") (pintype "passive"))
      (node (ref "JP3") (pin "5") (pinfunction "5_5") (pintype "passive"))
      (node (ref "JP3") (pin "6") (pinfunction "6_6") (pintype "passive"))
      (node (ref "JP4") (pin "5") (pinfunction "5_5") (pintype "passive"))
      (node (ref "JP4") (pin "6") (pinfunction "6_6") (pintype "passive"))
      (node (ref "JP5") (pin "8") (pinfunction "8_8") (pintype "passive"))
      (node (ref "JP6") (pin "4") (pinfunction "4_4") (pintype "passive"))
      (node (ref "JP8") (pin "5") (pinfunction "5_5") (pintype "passive"))
      (node (ref "JP9") (pin "5") (pinfunction "5_5") (pintype "passive"))
      (node (ref "Q1") (pin "2") (pinfunction "S_2") (pintype "passive"))
      (node (ref "Q10") (pin "2") (pinfunction "S_2") (pintype "passive"))
      (node (ref "Q11") (pin "2") (pinfunction "S_2") (pintype "passive"))
      (node (ref "Q12") (pin "2") (pinfunction "S_2") (pintype "passive"))
      (node (ref "Q13") (pin "2") (pinfunction "S_2") (pintype "passive"))
      (node (ref "Q14") (pin "2") (pinfunction "S_2") (pintype "passive"))
      (node (ref "Q15") (pin "2") (pinfunction "S_2") (pintype "passive"))
      (node (ref "Q16") (pin "2") (pinfunction "S_2") (pintype "passive"))
      (node (ref "Q2") (pin "2") (pinfunction "S_2") (pintype "passive"))
      (node (ref "Q3") (pin "2") (pinfunction "S_2") (pintype "passive"))
      (node (ref "Q4") (pin "2") (pinfunction "S_2") (pintype "passive"))
      (node (ref "Q5") (pin "2") (pinfunction "S_2") (pintype "passive"))
      (node (ref "Q6") (pin "2") (pinfunction "S_2") (pintype "passive"))
      (node (ref "Q7") (pin "2") (pinfunction "S_2") (pintype "passive"))
      (node (ref "Q8") (pin "2") (pinfunction "S_2") (pintype "passive"))
      (node (ref "Q9") (pin "2") (pinfunction "S_2") (pintype "passive"))
      (node (ref "R16") (pin "2") (pinfunction "2_2") (pintype "passive"))
      (node (ref "R51") (pin "1") (pinfunction "1_1") (pintype "passive"))
      (node (ref "SJ12") (pin "2") (pinfunction "2_2") (pintype "passive"))
      (node (ref "SJ13") (pin "P$2") (pinfunction "2_P$2") (pintype "passive"))
      (node (ref "SJ19") (pin "2") (pinfunction "2_2") (pintype "passive"))
      (node (ref "SJ20") (pin "P$2") (pinfunction "2_P$2") (pintype "passive"))
      (node (ref "U1") (pin "2") (pinfunction "GND_2") (pintype "power_in"))
      (node (ref "U10") (pin "3") (pinfunction "VSS_3") (pintype "power_in"))
      (node (ref "U11") (pin "13") (pinfunction "G_13") (pintype "input"))
      (node (ref "U11") (pin "8") (pinfunction "GND_8") (pintype "power_in"))
      (node (ref "U13") (pin "13") (pinfunction "G_13") (pintype "input"))
      (node (ref "U13") (pin "8") (pinfunction "GND_8") (pintype "power_in"))
      (node (ref "U1B") (pin "2") (pinfunction "VSS_2") (pintype "power_in"))
      (node (ref "U2") (pin "4") (pinfunction "SD_4") (pintype "bidirectional"))
      (node (ref "U2") (pin "5") (pinfunction "GND1_5") (pintype "power_in"))
      (node (ref "U2") (pin "6") (pinfunction "GND2_6") (pintype "power_in"))
      (node (ref "U2") (pin "7") (pinfunction "GND3_7") (pintype "power_in"))
      (node (ref "U2") (pin "8") (pinfunction "GND4_8") (pintype "power_in"))
      (node (ref "U2B") (pin "2") (pinfunction "GNDSIG_2") (pintype "input"))
      (node (ref "U2B") (pin "3") (pinfunction "~{ON/OFF}_3") (pintype "input"))
      (node (ref "U2B") (pin "4") (pinfunction "GND_4") (pintype "power_in"))
      (node (ref "U3") (pin "6") (pinfunction "INH_6") (pintype "input"))
      (node (ref "U3") (pin "8") (pinfunction "GND_8") (pintype "power_in"))
      (node (ref "U4") (pin "6") (pinfunction "INH_6") (pintype "input"))
      (node (ref "U4") (pin "8") (pinfunction "GND_8") (pintype "power_in"))
      (node (ref "U5") (pin "3") (pinfunction "VSS_3") (pintype "power_in"))
      (node (ref "U6") (pin "11") (pinfunction "V-_11") (pintype "power_in"))
      (node (ref "U7") (pin "3") (pinfunction "VSS_3") (pintype "power_in"))
      (node (ref "U8") (pin "3") (pinfunction "VSS_3") (pintype "power_in"))
      (node (ref "U9") (pin "11") (pinfunction "V-_11") (pintype "power_in"))
      (node (ref "X1") (pin "3") (pinfunction "3_3") (pintype "passive"))
      (node (ref "X1") (pin "6") (pinfunction "6_6") (pintype "passive"))
      (node (ref "X1") (pin "7") (pinfunction "7_7") (pintype "passive"))
      (node (ref "X2") (pin "3") (pinfunction "3_3") (pintype "passive"))
      (node (ref "X2") (pin "6") (pinfunction "6_6") (pintype "passive"))
      (node (ref "X2") (pin "7") (pinfunction "7_7") (pintype "passive"))
      (node (ref "X3") (pin "2") (pinfunction "2_2") (pintype "passive"))
      (node (ref "X5") (pin "9") (pinfunction "9_9") (pintype "passive"))
      (node (ref "X6") (pin "2") (pinfunction "2_2") (pintype "passive"))
    )
    (net (code "18") (name "I2CSCL") (class "Default")
      (node (ref "G1") (pin "PB6") (pinfunction "PB6_PB6") (pintype "bidirectional"))
      (node (ref "JP6") (pin "1") (pinfunction "1_1") (pintype "passive"))
      (node (ref "R15") (pin "2") (pinfunction "2_2") (pintype "passive"))
    )
    (net (code "19") (name "I2CSDA") (class "Default")
      (node (ref "G1") (pin "PB7") (pinfunction "PB7_PB7") (pintype "bidirectional"))
      (node (ref "JP6") (pin "2") (pinfunction "2_2") (pintype "passive"))
      (node (ref "R14") (pin "2") (pinfunction "2_2") (pintype "passive"))
    )
    (net (code "20") (name "ILAT") (class "Default")
      (node (ref "G1") (pin "PA6") (pinfunction "PA6_PA6") (pintype "bidirectional"))
      (node (ref "U3") (pin "15") (pinfunction "SH/~{LD}_15") (pintype "input"))
      (node (ref "U4") (pin "15") (pinfunction "SH/~{LD}_15") (pintype "input"))
    )
    (net (code "21") (name "MISO") (class "Default")
      (node (ref "G1") (pin "PB4") (pinfunction "PB4_PB4") (pintype "bidirectional"))
      (node (ref "JP5") (pin "1") (pinfunction "1_1") (pintype "passive"))
    )
    (net (code "22") (name "MISO2") (class "Default")
      (node (ref "G1") (pin "PC2") (pinfunction "PC2_PC2") (pintype "bidirectional"))
      (node (ref "SJ1") (pin "P$2") (pinfunction "2_P$2") (pintype "passive"))
      (node (ref "SJ7") (pin "P$2") (pinfunction "2_P$2") (pintype "passive"))
      (node (ref "U3") (pin "13") (pinfunction "QH_13") (pintype "output"))
    )
    (net (code "23") (name "MOSI") (class "Default")
      (node (ref "G1") (pin "PB5") (pinfunction "PB5_PB5") (pintype "bidirectional"))
      (node (ref "R4") (pin "1") (pinfunction "1_1") (pintype "passive"))
      (node (ref "SJ14") (pin "P$2") (pinfunction "2_P$2") (pintype "passive"))
      (node (ref "SJ4") (pin "1") (pinfunction "1_1") (pintype "passive"))
      (node (ref "U13") (pin "14") (pinfunction "SER_14") (pintype "input"))
    )
    (net (code "24") (name "Net-(D1-PadA)") (class "Default")
      (node (ref "D1") (pin "A") (pinfunction "A_A") (pintype "passive"))
      (node (ref "D2") (pin "A") (pinfunction "A_A") (pintype "passive"))
      (node (ref "JP7") (pin "4") (pinfunction "4_4") (pintype "passive"))
    )
    (net (code "25") (name "Net-(D1-PadC)") (class "Default")
      (node (ref "D1") (pin "C") (pinfunction "C_C") (pintype "passive"))
      (node (ref "D2") (pin "C") (pinfunction "C_C") (pintype "passive"))
      (node (ref "JP7") (pin "1") (pinfunction "1_1") (pintype "passive"))
    )
    (net (code "26") (name "Net-(D3-PadA)") (class "Default")
      (node (ref "D3") (pin "A") (pinfunction "A_A") (pintype "passive"))
      (node (ref "D4") (pin "A") (pinfunction "A_A") (pintype "passive"))
      (node (ref "J1") (pin "1") (pinfunction "1_1") (pintype "passive"))
      (node (ref "J1") (pin "1B") (pinfunction "1B_1B") (pintype "passive"))
      (node (ref "X3") (pin "1") (pinfunction "1_1") (pintype "passive"))
    )
    (net (code "27") (name "Net-(JP7-Pad3)") (class "Default")
      (node (ref "JP7") (pin "3") (pinfunction "3_3") (pintype "passive"))
      (node (ref "R17") (pin "1") (pinfunction "1_1") (pintype "passive"))
    )
    (net (code "28") (name "Net-(JP8-Pad10)") (class "Default")
      (node (ref "JP8") (pin "10") (pinfunction "10_10") (pintype "passive"))
      (node (ref "R25") (pin "2") (pinfunction "2_2") (pintype "passive"))
      (node (ref "R26") (pin "2") (pinfunction "2_2") (pintype "passive"))
      (node (ref "RN1") (pin "9") (pinfunction "9_9") (pintype "passive"))
      (node (ref "RN2") (pin "1") (pinfunction "1_1") (pintype "passive"))
      (node (ref "X4") (pin "1") (pinfunction "1_1") (pintype "passive"))
    )
    (net (code "29") (name "Net-(JP9-Pad10)") (class "Default")
      (node (ref "JP9") (pin "10") (pinfunction "10_10") (pintype "passive"))
      (node (ref "R41") (pin "2") (pinfunction "2_2") (pintype "passive"))
      (node (ref "R42") (pin "2") (pinfunction "2_2") (pintype "passive"))
      (node (ref "RN3") (pin "9") (pinfunction "9_9") (pintype "passive"))
      (node (ref "RN4") (pin "1") (pinfunction "1_1") (pintype "passive"))
      (node (ref "X5") (pin "1") (pinfunction "1_1") (pintype "passive"))
    )
    (net (code "30") (name "Net-(Q1-D)") (class "Default")
      (node (ref "Q1") (pin "3") (pinfunction "D_3") (pintype "passive"))
      (node (ref "U12") (pin "11") (pinfunction "O8_11") (pintype "open_collector"))
      (node (ref "X8") (pin "8") (pinfunction "8_8") (pintype "passive"))
    )
    (net (code "31") (name "Net-(Q1-G)") (class "Default")
      (node (ref "Q1") (pin "1") (pinfunction "G_1") (pintype "passive"))
      (node (ref "R52") (pin "2") (pinfunction "2_2") (pintype "passive"))
    )
    (net (code "32") (name "Net-(Q2-D)") (class "Default")
      (node (ref "Q2") (pin "3") (pinfunction "D_3") (pintype "passive"))
      (node (ref "U12") (pin "12") (pinfunction "O7_12") (pintype "open_collector"))
      (node (ref "X8") (pin "7") (pinfunction "7_7") (pintype "passive"))
    )
    (net (code "33") (name "Net-(Q2-G)") (class "Default")
      (node (ref "Q2") (pin "1") (pinfunction "G_1") (pintype "passive"))
      (node (ref "R53") (pin "2") (pinfunction "2_2") (pintype "passive"))
    )
    (net (code "34") (name "Net-(Q3-D)") (class "Default")
      (node (ref "Q3") (pin "3") (pinfunction "D_3") (pintype "passive"))
      (node (ref "U12") (pin "13") (pinfunction "O6_13") (pintype "open_collector"))
      (node (ref "X8") (pin "6") (pinfunction "6_6") (pintype "passive"))
    )
    (net (code "35") (name "Net-(Q3-G)") (class "Default")
      (node (ref "Q3") (pin "1") (pinfunction "G_1") (pintype "passive"))
      (node (ref "R54") (pin "2") (pinfunction "2_2") (pintype "passive"))
    )
    (net (code "36") (name "Net-(Q4-D)") (class "Default")
      (node (ref "Q4") (pin "3") (pinfunction "D_3") (pintype "passive"))
      (node (ref "U12") (pin "14") (pinfunction "O5_14") (pintype "open_collector"))
      (node (ref "X8") (pin "5") (pinfunction "5_5") (pintype "passive"))
    )
    (net (code "37") (name "Net-(Q4-G)") (class "Default")
      (node (ref "Q4") (pin "1") (pinfunction "G_1") (pintype "passive"))
      (node (ref "R55") (pin "2") (pinfunction "2_2") (pintype "passive"))
    )
    (net (code "38") (name "Net-(Q5-D)") (class "Default")
      (node (ref "Q5") (pin "3") (pinfunction "D_3") (pintype "passive"))
      (node (ref "U12") (pin "15") (pinfunction "O4_15") (pintype "open_collector"))
      (node (ref "X8") (pin "4") (pinfunction "4_4") (pintype "passive"))
    )
    (net (code "39") (name "Net-(Q5-G)") (class "Default")
      (node (ref "Q5") (pin "1") (pinfunction "G_1") (pintype "passive"))
      (node (ref "R56") (pin "2") (pinfunction "2_2") (pintype "passive"))
    )
    (net (code "40") (name "Net-(Q6-D)") (class "Default")
      (node (ref "Q6") (pin "3") (pinfunction "D_3") (pintype "passive"))
      (node (ref "U12") (pin "16") (pinfunction "O3_16") (pintype "open_collector"))
      (node (ref "X8") (pin "3") (pinfunction "3_3") (pintype "passive"))
    )
    (net (code "41") (name "Net-(Q6-G)") (class "Default")
      (node (ref "Q6") (pin "1") (pinfunction "G_1") (pintype "passive"))
      (node (ref "R57") (pin "2") (pinfunction "2_2") (pintype "passive"))
    )
    (net (code "42") (name "Net-(Q7-D)") (class "Default")
      (node (ref "Q7") (pin "3") (pinfunction "D_3") (pintype "passive"))
      (node (ref "U12") (pin "17") (pinfunction "O2_17") (pintype "open_collector"))
      (node (ref "X8") (pin "2") (pinfunction "2_2") (pintype "passive"))
    )
    (net (code "43") (name "Net-(Q7-G)") (class "Default")
      (node (ref "Q7") (pin "1") (pinfunction "G_1") (pintype "passive"))
      (node (ref "R58") (pin "2") (pinfunction "2_2") (pintype "passive"))
    )
    (net (code "44") (name "Net-(Q8-D)") (class "Default")
      (node (ref "Q8") (pin "3") (pinfunction "D_3") (pintype "passive"))
      (node (ref "U12") (pin "18") (pinfunction "O1_18") (pintype "open_collector"))
      (node (ref "X8") (pin "1") (pinfunction "1_1") (pintype "passive"))
    )
    (net (code "45") (name "Net-(Q8-G)") (class "Default")
      (node (ref "Q8") (pin "1") (pinfunction "G_1") (pintype "passive"))
      (node (ref "R59") (pin "2") (pinfunction "2_2") (pintype "passive"))
    )
    (net (code "46") (name "Net-(Q9-D)") (class "Default")
      (node (ref "Q9") (pin "3") (pinfunction "D_3") (pintype "passive"))
      (node (ref "U14") (pin "11") (pinfunction "O8_11") (pintype "open_collector"))
      (node (ref "X9") (pin "8") (pinfunction "8_8") (pintype "passive"))
    )
    (net (code "47") (name "Net-(Q9-G)") (class "Default")
      (node (ref "Q9") (pin "1") (pinfunction "G_1") (pintype "passive"))
      (node (ref "R60") (pin "2") (pinfunction "2_2") (pintype "passive"))
    )
    (net (code "48") (name "Net-(Q10-D)") (class "Default")
      (node (ref "Q10") (pin "3") (pinfunction "D_3") (pintype "passive"))
      (node (ref "U14") (pin "12") (pinfunction "O7_12") (pintype "open_collector"))
      (node (ref "X9") (pin "7") (pinfunction "7_7") (pintype "passive"))
    )
    (net (code "49") (name "Net-(Q10-G)") (class "Default")
      (node (ref "Q10") (pin "1") (pinfunction "G_1") (pintype "passive"))
      (node (ref "R61") (pin "2") (pinfunction "2_2") (pintype "passive"))
    )
    (net (code "50") (name "Net-(Q11-D)") (class "Default")
      (node (ref "Q11") (pin "3") (pinfunction "D_3") (pintype "passive"))
      (node (ref "U14") (pin "13") (pinfunction "O6_13") (pintype "open_collector"))
      (node (ref "X9") (pin "6") (pinfunction "6_6") (pintype "passive"))
    )
    (net (code "51") (name "Net-(Q11-G)") (class "Default")
      (node (ref "Q11") (pin "1") (pinfunction "G_1") (pintype "passive"))
      (node (ref "R62") (pin "2") (pinfunction "2_2") (pintype "passive"))
    )
    (net (code "52") (name "Net-(Q12-D)") (class "Default")
      (node (ref "Q12") (pin "3") (pinfunction "D_3") (pintype "passive"))
      (node (ref "U14") (pin "14") (pinfunction "O5_14") (pintype "open_collector"))
      (node (ref "X9") (pin "5") (pinfunction "5_5") (pintype "passive"))
    )
    (net (code "53") (name "Net-(Q12-G)") (class "Default")
      (node (ref "Q12") (pin "1") (pinfunction "G_1") (pintype "passive"))
      (node (ref "R63") (pin "2") (pinfunction "2_2") (pintype "passive"))
    )
    (net (code "54") (name "Net-(Q13-D)") (class "Default")
      (node (ref "Q13") (pin "3") (pinfunction "D_3") (pintype "passive"))
      (node (ref "U14") (pin "15") (pinfunction "O4_15") (pintype "open_collector"))
      (node (ref "X9") (pin "4") (pinfunction "4_4") (pintype "passive"))
    )
    (net (code "55") (name "Net-(Q13-G)") (class "Default")
      (node (ref "Q13") (pin "1") (pinfunction "G_1") (pintype "passive"))
      (node (ref "R64") (pin "2") (pinfunction "2_2") (pintype "passive"))
    )
    (net (code "56") (name "Net-(Q14-D)") (class "Default")
      (node (ref "Q14") (pin "3") (pinfunction "D_3") (pintype "passive"))
      (node (ref "U14") (pin "16") (pinfunction "O3_16") (pintype "open_collector"))
      (node (ref "X9") (pin "3") (pinfunction "3_3") (pintype "passive"))
    )
    (net (code "57") (name "Net-(Q14-G)") (class "Default")
      (node (ref "Q14") (pin "1") (pinfunction "G_1") (pintype "passive"))
      (node (ref "R65") (pin "2") (pinfunction "2_2") (pintype "passive"))
    )
    (net (code "58") (name "Net-(Q15-D)") (class "Default")
      (node (ref "Q15") (pin "3") (pinfunction "D_3") (pintype "passive"))
      (node (ref "U14") (pin "17") (pinfunction "O2_17") (pintype "open_collector"))
      (node (ref "X9") (pin "2") (pinfunction "2_2") (pintype "passive"))
    )
    (net (code "59") (name "Net-(Q15-G)") (class "Default")
      (node (ref "Q15") (pin "1") (pinfunction "G_1") (pintype "passive"))
      (node (ref "R66") (pin "2") (pinfunction "2_2") (pintype "passive"))
    )
    (net (code "60") (name "Net-(Q16-D)") (class "Default")
      (node (ref "Q16") (pin "3") (pinfunction "D_3") (pintype "passive"))
      (node (ref "U14") (pin "18") (pinfunction "O1_18") (pintype "open_collector"))
      (node (ref "X9") (pin "1") (pinfunction "1_1") (pintype "passive"))
    )
    (net (code "61") (name "Net-(Q16-G)") (class "Default")
      (node (ref "Q16") (pin "1") (pinfunction "G_1") (pintype "passive"))
      (node (ref "R67") (pin "2") (pinfunction "2_2") (pintype "passive"))
    )
    (net (code "62") (name "Net-(RN2A-2)") (class "Default")
      (node (ref "R25") (pin "1") (pinfunction "1_1") (pintype "passive"))
      (node (ref "RN2") (pin "16") (pinfunction "2_16") (pintype "passive"))
      (node (ref "U3") (pin "14") (pinfunction "H_14") (pintype "input"))
    )
    (net (code "63") (name "Net-(RN2B-1)") (class "Default")
      (node (ref "JP8") (pin "9") (pinfunction "9_9") (pintype "passive"))
      (node (ref "R24") (pin "2") (pinfunction "2_2") (pintype "passive"))
      (node (ref "R27") (pin "2") (pinfunction "2_2") (pintype "passive"))
      (node (ref "RN1") (pin "8") (pinfunction "8_8") (pintype "passive"))
      (node (ref "RN2") (pin "2") (pinfunction "1_2") (pintype "passive"))
      (node (ref "X4") (pin "2") (pinfunction "2_2") (pintype "passive"))
    )
    (net (code "64") (name "Net-(RN2B-2)") (class "Default")
      (node (ref "R24") (pin "1") (pinfunction "1_1") (pintype "passive"))
      (node (ref "RN2") (pin "15") (pinfunction "2_15") (pintype "passive"))
      (node (ref "U3") (pin "12") (pinfunction "G_12") (pintype "input"))
    )
    (net (code "65") (name "Net-(RN2C-1)") (class "Default")
      (node (ref "JP8") (pin "8") (pinfunction "8_8") (pintype "passive"))
      (node (ref "R23") (pin "2") (pinfunction "2_2") (pintype "passive"))
      (node (ref "R28") (pin "2") (pinfunction "2_2") (pintype "passive"))
      (node (ref "RN1") (pin "7") (pinfunction "7_7") (pintype "passive"))
      (node (ref "RN2") (pin "3") (pinfunction "1_3") (pintype "passive"))
      (node (ref "X4") (pin "3") (pinfunction "3_3") (pintype "passive"))
    )
    (net (code "66") (name "Net-(RN2C-2)") (class "Default")
      (node (ref "R23") (pin "1") (pinfunction "1_1") (pintype "passive"))
      (node (ref "RN2") (pin "14") (pinfunction "2_14") (pintype "passive"))
      (node (ref "U3") (pin "11") (pinfunction "F_11") (pintype "input"))
    )
    (net (code "67") (name "Net-(RN2D-1)") (class "Default")
      (node (ref "JP8") (pin "7") (pinfunction "7_7") (pintype "passive"))
      (node (ref "R22") (pin "2") (pinfunction "2_2") (pintype "passive"))
      (node (ref "R29") (pin "2") (pinfunction "2_2") (pintype "passive"))
      (node (ref "RN1") (pin "6") (pinfunction "6_6") (pintype "passive"))
      (node (ref "RN2") (pin "4") (pinfunction "1_4") (pintype "passive"))
      (node (ref "X4") (pin "4") (pinfunction "4_4") (pintype "passive"))
    )
    (net (code "68") (name "Net-(RN2D-2)") (class "Default")
      (node (ref "R22") (pin "1") (pinfunction "1_1") (pintype "passive"))
      (node (ref "RN2") (pin "13") (pinfunction "2_13") (pintype "passive"))
      (node (ref "U3") (pin "10") (pinfunction "E_10") (pintype "input"))
    )
    (net (code "69") (name "Net-(RN2E-1)") (class "Default")
      (node (ref "JP8") (pin "4") (pinfunction "4_4") (pintype "passive"))
      (node (ref "R21") (pin "2") (pinfunction "2_2") (pintype "passive"))
      (node (ref "R30") (pin "2") (pinfunction "2_2") (pintype "passive"))
      (node (ref "RN1") (pin "5") (pinfunction "5_5") (pintype "passive"))
      (node (ref "RN2") (pin "5") (pinfunction "1_5") (pintype "passive"))
      (node (ref "X4") (pin "5") (pinfunction "5_5") (pintype "passive"))
    )
    (net (code "70") (name "Net-(RN2E-2)") (class "Default")
      (node (ref "R21") (pin "1") (pinfunction "1_1") (pintype "passive"))
      (node (ref "RN2") (pin "12") (pinfunction "2_12") (pintype "passive"))
      (node (ref "U3") (pin "5") (pinfunction "D_5") (pintype "input"))
    )
    (net (code "71") (name "Net-(RN2F-1)") (class "Default")
      (node (ref "JP8") (pin "3") (pinfunction "3_3") (pintype "passive"))
      (node (ref "R20") (pin "2") (pinfunction "2_2") (pintype "passive"))
      (node (ref "R31") (pin "2") (pinfunction "2_2") (pintype "passive"))
      (node (ref "RN1") (pin "4") (pinfunction "4_4") (pintype "passive"))
      (node (ref "RN2") (pin "6") (pinfunction "1_6") (pintype "passive"))
      (node (ref "X4") (pin "6") (pinfunction "6_6") (pintype "passive"))
    )
    (net (code "72") (name "Net-(RN2F-2)") (class "Default")
      (node (ref "R20") (pin "1") (pinfunction "1_1") (pintype "passive"))
      (node (ref "RN2") (pin "11") (pinfunction "2_11") (pintype "passive"))
      (node (ref "U3") (pin "4") (pinfunction "C_4") (pintype "input"))
    )
    (net (code "73") (name "Net-(RN2G-1)") (class "Default")
      (node (ref "JP8") (pin "2") (pinfunction "2_2") (pintype "passive"))
      (node (ref "R19") (pin "2") (pinfunction "2_2") (pintype "passive"))
      (node (ref "R32") (pin "2") (pinfunction "2_2") (pintype "passive"))
      (node (ref "RN1") (pin "3") (pinfunction "3_3") (pintype "passive"))
      (node (ref "RN2") (pin "7") (pinfunction "1_7") (pintype "passive"))
      (node (ref "X4") (pin "7") (pinfunction "7_7") (pintype "passive"))
    )
    (net (code "74") (name "Net-(RN2G-2)") (class "Default")
      (node (ref "R19") (pin "1") (pinfunction "1_1") (pintype "passive"))
      (node (ref "RN2") (pin "10") (pinfunction "2_10") (pintype "passive"))
      (node (ref "U3") (pin "3") (pinfunction "B_3") (pintype "input"))
    )
    (net (code "75") (name "Net-(RN2H-1)") (class "Default")
      (node (ref "JP8") (pin "1") (pinfunction "1_1") (pintype "passive"))
      (node (ref "R18") (pin "2") (pinfunction "2_2") (pintype "passive"))
      (node (ref "R33") (pin "2") (pinfunction "2_2") (pintype "passive"))
      (node (ref "RN1") (pin "2") (pinfunction "2_2") (pintype "passive"))
      (node (ref "RN2") (pin "8") (pinfunction "1_8") (pintype "passive"))
      (node (ref "X4") (pin "8") (pinfunction "8_8") (pintype "passive"))
    )
    (net (code "76") (name "Net-(RN2H-2)") (class "Default")
      (node (ref "R18") (pin "1") (pinfunction "1_1") (pintype "passive"))
      (node (ref "RN2") (pin "9") (pinfunction "2_9") (pintype "passive"))
      (node (ref "U3") (pin "2") (pinfunction "A_2") (pintype "input"))
    )
    (net (code "77") (name "Net-(RN4A-2)") (class "Default")
      (node (ref "R41") (pin "1") (pinfunction "1_1") (pintype "passive"))
      (node (ref "RN4") (pin "16") (pinfunction "2_16") (pintype "passive"))
      (node (ref "U4") (pin "14") (pinfunction "H_14") (pintype "input"))
    )
    (net (code "78") (name "Net-(RN4B-1)") (class "Default")
      (node (ref "JP9") (pin "9") (pinfunction "9_9") (pintype "passive"))
      (node (ref "R40") (pin "2") (pinfunction "2_2") (pintype "passive"))
      (node (ref "R43") (pin "2") (pinfunction "2_2") (pintype "passive"))
      (node (ref "RN3") (pin "8") (pinfunction "8_8") (pintype "passive"))
      (node (ref "RN4") (pin "2") (pinfunction "1_2") (pintype "passive"))
      (node (ref "X5") (pin "2") (pinfunction "2_2") (pintype "passive"))
    )
    (net (code "79") (name "Net-(RN4B-2)") (class "Default")
      (node (ref "R40") (pin "1") (pinfunction "1_1") (pintype "passive"))
      (node (ref "RN4") (pin "15") (pinfunction "2_15") (pintype "passive"))
      (node (ref "U4") (pin "12") (pinfunction "G_12") (pintype "input"))
    )
    (net (code "80") (name "Net-(RN4C-1)") (class "Default")
      (node (ref "JP9") (pin "8") (pinfunction "8_8") (pintype "passive"))
      (node (ref "R39") (pin "2") (pinfunction "2_2") (pintype "passive"))
      (node (ref "R44") (pin "2") (pinfunction "2_2") (pintype "passive"))
      (node (ref "RN3") (pin "7") (pinfunction "7_7") (pintype "passive"))
      (node (ref "RN4") (pin "3") (pinfunction "1_3") (pintype "passive"))
      (node (ref "X5") (pin "3") (pinfunction "3_3") (pintype "passive"))
    )
    (net (code "81") (name "Net-(RN4C-2)") (class "Default")
      (node (ref "R39") (pin "1") (pinfunction "1_1") (pintype "passive"))
      (node (ref "RN4") (pin "14") (pinfunction "2_14") (pintype "passive"))
      (node (ref "U4") (pin "11") (pinfunction "F_11") (pintype "input"))
    )
    (net (code "82") (name "Net-(RN4D-1)") (class "Default")
      (node (ref "JP9") (pin "7") (pinfunction "7_7") (pintype "passive"))
      (node (ref "R38") (pin "2") (pinfunction "2_2") (pintype "passive"))
      (node (ref "R45") (pin "2") (pinfunction "2_2") (pintype "passive"))
      (node (ref "RN3") (pin "6") (pinfunction "6_6") (pintype "passive"))
      (node (ref "RN4") (pin "4") (pinfunction "1_4") (pintype "passive"))
      (node (ref "X5") (pin "4") (pinfunction "4_4") (pintype "passive"))
    )
    (net (code "83") (name "Net-(RN4D-2)") (class "Default")
      (node (ref "R38") (pin "1") (pinfunction "1_1") (pintype "passive"))
      (node (ref "RN4") (pin "13") (pinfunction "2_13") (pintype "passive"))
      (node (ref "U4") (pin "10") (pinfunction "E_10") (pintype "input"))
    )
    (net (code "84") (name "Net-(RN4E-1)") (class "Default")
      (node (ref "JP9") (pin "4") (pinfunction "4_4") (pintype "passive"))
      (node (ref "R37") (pin "2") (pinfunction "2_2") (pintype "passive"))
      (node (ref "R46") (pin "2") (pinfunction "2_2") (pintype "passive"))
      (node (ref "RN3") (pin "5") (pinfunction "5_5") (pintype "passive"))
      (node (ref "RN4") (pin "5") (pinfunction "1_5") (pintype "passive"))
      (node (ref "X5") (pin "5") (pinfunction "5_5") (pintype "passive"))
    )
    (net (code "85") (name "Net-(RN4E-2)") (class "Default")
      (node (ref "R37") (pin "1") (pinfunction "1_1") (pintype "passive"))
      (node (ref "RN4") (pin "12") (pinfunction "2_12") (pintype "passive"))
      (node (ref "U4") (pin "5") (pinfunction "D_5") (pintype "input"))
    )
    (net (code "86") (name "Net-(RN4F-1)") (class "Default")
      (node (ref "JP9") (pin "3") (pinfunction "3_3") (pintype "passive"))
      (node (ref "R36") (pin "2") (pinfunction "2_2") (pintype "passive"))
      (node (ref "R47") (pin "2") (pinfunction "2_2") (pintype "passive"))
      (node (ref "RN3") (pin "4") (pinfunction "4_4") (pintype "passive"))
      (node (ref "RN4") (pin "6") (pinfunction "1_6") (pintype "passive"))
      (node (ref "X5") (pin "6") (pinfunction "6_6") (pintype "passive"))
    )
    (net (code "87") (name "Net-(RN4F-2)") (class "Default")
      (node (ref "R36") (pin "1") (pinfunction "1_1") (pintype "passive"))
      (node (ref "RN4") (pin "11") (pinfunction "2_11") (pintype "passive"))
      (node (ref "U4") (pin "4") (pinfunction "C_4") (pintype "input"))
    )
    (net (code "88") (name "Net-(RN4G-1)") (class "Default")
      (node (ref "JP9") (pin "2") (pinfunction "2_2") (pintype "passive"))
      (node (ref "R35") (pin "2") (pinfunction "2_2") (pintype "passive"))
      (node (ref "R48") (pin "2") (pinfunction "2_2") (pintype "passive"))
      (node (ref "RN3") (pin "3") (pinfunction "3_3") (pintype "passive"))
      (node (ref "RN4") (pin "7") (pinfunction "1_7") (pintype "passive"))
      (node (ref "X5") (pin "7") (pinfunction "7_7") (pintype "passive"))
    )
    (net (code "89") (name "Net-(RN4G-2)") (class "Default")
      (node (ref "R35") (pin "1") (pinfunction "1_1") (pintype "passive"))
      (node (ref "RN4") (pin "10") (pinfunction "2_10") (pintype "passive"))
      (node (ref "U4") (pin "3") (pinfunction "B_3") (pintype "input"))
    )
    (net (code "90") (name "Net-(RN4H-1)") (class "Default")
      (node (ref "JP9") (pin "1") (pinfunction "1_1") (pintype "passive"))
      (node (ref "R34") (pin "2") (pinfunction "2_2") (pintype "passive"))
      (node (ref "R49") (pin "2") (pinfunction "2_2") (pintype "passive"))
      (node (ref "RN3") (pin "2") (pinfunction "2_2") (pintype "passive"))
      (node (ref "RN4") (pin "8") (pinfunction "1_8") (pintype "passive"))
      (node (ref "X5") (pin "8") (pinfunction "8_8") (pintype "passive"))
    )
    (net (code "91") (name "Net-(RN4H-2)") (class "Default")
      (node (ref "R34") (pin "1") (pinfunction "1_1") (pintype "passive"))
      (node (ref "RN4") (pin "9") (pinfunction "2_9") (pintype "passive"))
      (node (ref "U4") (pin "2") (pinfunction "A_2") (pintype "input"))
    )
    (net (code "92") (name "Net-(SJ1-1)") (class "Default")
      (node (ref "G1") (pin "PB14") (pinfunction "PB14_PB14") (pintype "bidirectional"))
      (node (ref "SJ1") (pin "P$1") (pinfunction "1_P$1") (pintype "passive"))
    )
    (net (code "93") (name "Net-(SJ2-2)") (class "Default")
      (node (ref "G1") (pin "PB13") (pinfunction "PB13_PB13") (pintype "bidirectional"))
      (node (ref "SJ2") (pin "P$2") (pinfunction "2_P$2") (pintype "passive"))
    )
    (net (code "94") (name "Net-(SJ3-1)") (class "Default")
      (node (ref "G1") (pin "VIN2") (pinfunction "VIN2_VIN2") (pintype "power_in"))
      (node (ref "SJ3") (pin "P$1") (pinfunction "1_P$1") (pintype "passive"))
    )
    (net (code "95") (name "Net-(SJ5-2)") (class "Default")
      (node (ref "JP5") (pin "2") (pinfunction "2_2") (pintype "passive"))
      (node (ref "SJ4") (pin "2") (pinfunction "2_2") (pintype "passive"))
      (node (ref "SJ5") (pin "P$2") (pinfunction "2_P$2") (pintype "passive"))
    )
    (net (code "96") (name "Net-(SJ6-1)") (class "Default")
      (node (ref "SJ6") (pin "P$1") (pinfunction "1_P$1") (pintype "passive"))
      (node (ref "U1") (pin "5") (pinfunction "VREF_5") (pintype "output"))
      (node (ref "U1B") (pin "5") (pinfunction "VREF_5") (pintype "bidirectional"))
    )
    (net (code "97") (name "Net-(SJ10-1)") (class "Default")
      (node (ref "SJ10") (pin "P$1") (pinfunction "1_P$1") (pintype "passive"))
      (node (ref "SJ12") (pin "1") (pinfunction "1_1") (pintype "passive"))
      (node (ref "SJ8") (pin "P$1") (pinfunction "1_P$1") (pintype "passive"))
      (node (ref "U12") (pin "9") (pinfunction "GND_9") (pintype "power_in"))
    )
    (net (code "98") (name "Net-(SJ11-1)") (class "Default")
      (node (ref "SJ11") (pin "P$1") (pinfunction "1_P$1") (pintype "passive"))
      (node (ref "SJ13") (pin "P$1") (pinfunction "1_P$1") (pintype "passive"))
      (node (ref "SJ9") (pin "P$1") (pinfunction "1_P$1") (pintype "passive"))
      (node (ref "U12") (pin "10") (pinfunction "CD+_10") (pintype "passive"))
      (node (ref "X8") (pin "9") (pinfunction "9_9") (pintype "passive"))
    )
    (net (code "99") (name "Net-(SJ15-1)") (class "Default")
      (node (ref "SJ15") (pin "P$1") (pinfunction "1_P$1") (pintype "passive"))
      (node (ref "SJ17") (pin "P$1") (pinfunction "1_P$1") (pintype "passive"))
      (node (ref "SJ19") (pin "1") (pinfunction "1_1") (pintype "passive"))
      (node (ref "U14") (pin "9") (pinfunction "GND_9") (pintype "power_in"))
    )
    (net (code "100") (name "Net-(SJ16-1)") (class "Default")
      (node (ref "SJ16") (pin "P$1") (pinfunction "1_P$1") (pintype "passive"))
      (node (ref "SJ18") (pin "P$1") (pinfunction "1_P$1") (pintype "passive"))
      (node (ref "SJ20") (pin "P$1") (pinfunction "1_P$1") (pintype "passive"))
      (node (ref "U14") (pin "10") (pinfunction "CD+_10") (pintype "passive"))
      (node (ref "X9") (pin "9") (pinfunction "9_9") (pintype "passive"))
    )
    (net (code "101") (name "Net-(U1-RS)") (class "Default")
      (node (ref "R16") (pin "1") (pinfunction "1_1") (pintype "passive"))
      (node (ref "U1") (pin "8") (pinfunction "RS_8") (pintype "input"))
      (node (ref "U1B") (pin "8") (pinfunction "RS_8") (pintype "bidirectional"))
    )
    (net (code "102") (name "Net-(U2-VOUT)") (class "Default")
      (node (ref "D5") (pin "C") (pinfunction "C_C") (pintype "passive"))
      (node (ref "D6") (pin "C") (pinfunction "C_C") (pintype "passive"))
      (node (ref "L1") (pin "2") (pinfunction "2_2") (pintype "passive"))
      (node (ref "U2") (pin "2") (pinfunction "VOUT_2") (pintype "bidirectional"))
      (node (ref "U2B") (pin "7") (pinfunction "OUT_7") (pintype "passive"))
    )
    (net (code "103") (name "Net-(U5A-O)") (class "Default")
      (node (ref "JP10") (pin "10") (pinfunction "10_10") (pintype "passive"))
      (node (ref "U5") (pin "7") (pinfunction "O_7") (pintype "output"))
      (node (ref "U6") (pin "7") (pinfunction "OUT_7") (pintype "output"))
      (node (ref "X7") (pin "1") (pinfunction "1_1") (pintype "passive"))
    )
    (net (code "104") (name "Net-(U5B-O)") (class "Default")
      (node (ref "JP10") (pin "9") (pinfunction "9_9") (pintype "passive"))
      (node (ref "U5") (pin "5") (pinfunction "O_5") (pintype "output"))
      (node (ref "U6") (pin "8") (pinfunction "OUT_8") (pintype "output"))
      (node (ref "X7") (pin "2") (pinfunction "2_2") (pintype "passive"))
    )
    (net (code "105") (name "Net-(U6A--IN)") (class "Default")
      (node (ref "R50") (pin "1") (pinfunction "1_1") (pintype "passive"))
      (node (ref "R51") (pin "2") (pinfunction "2_2") (pintype "passive"))
      (node (ref "U6") (pin "13") (pinfunction "-IN_13") (pintype "input"))
      (node (ref "U6") (pin "2") (pinfunction "-IN_2") (pintype "input"))
      (node (ref "U6") (pin "6") (pinfunction "-IN_6") (pintype "input"))
      (node (ref "U6") (pin "9") (pinfunction "-IN_9") (pintype "input"))
      (node (ref "U9") (pin "13") (pinfunction "-IN_13") (pintype "input"))
      (node (ref "U9") (pin "2") (pinfunction "-IN_2") (pintype "input"))
      (node (ref "U9") (pin "6") (pinfunction "-IN_6") (pintype "input"))
      (node (ref "U9") (pin "9") (pinfunction "-IN_9") (pintype "input"))
    )
    (net (code "106") (name "Net-(U6A-OUT)") (class "Default")
      (node (ref "JP10") (pin "8") (pinfunction "8_8") (pintype "passive"))
      (node (ref "U6") (pin "1") (pinfunction "OUT_1") (pintype "output"))
      (node (ref "U7") (pin "5") (pinfunction "O_5") (pintype "output"))
      (node (ref "X7") (pin "3") (pinfunction "3_3") (pintype "passive"))
    )
    (net (code "107") (name "Net-(U6D-OUT)") (class "Default")
      (node (ref "JP10") (pin "7") (pinfunction "7_7") (pintype "passive"))
      (node (ref "U6") (pin "14") (pinfunction "OUT_14") (pintype "output"))
      (node (ref "U7") (pin "7") (pinfunction "O_7") (pintype "output"))
      (node (ref "X7") (pin "4") (pinfunction "4_4") (pintype "passive"))
    )
    (net (code "108") (name "Net-(U8A-O)") (class "Default")
      (node (ref "JP10") (pin "4") (pinfunction "4_4") (pintype "passive"))
      (node (ref "U8") (pin "7") (pinfunction "O_7") (pintype "output"))
      (node (ref "U9") (pin "7") (pinfunction "OUT_7") (pintype "output"))
      (node (ref "X7") (pin "5") (pinfunction "5_5") (pintype "passive"))
    )
    (net (code "109") (name "Net-(U8B-O)") (class "Default")
      (node (ref "JP10") (pin "3") (pinfunction "3_3") (pintype "passive"))
      (node (ref "U8") (pin "5") (pinfunction "O_5") (pintype "output"))
      (node (ref "U9") (pin "8") (pinfunction "OUT_8") (pintype "output"))
      (node (ref "X7") (pin "6") (pinfunction "6_6") (pintype "passive"))
    )
    (net (code "110") (name "Net-(U10A-O)") (class "Default")
      (node (ref "JP10") (pin "1") (pinfunction "1_1") (pintype "passive"))
      (node (ref "U10") (pin "7") (pinfunction "O_7") (pintype "output"))
      (node (ref "U9") (pin "14") (pinfunction "OUT_14") (pintype "output"))
      (node (ref "X7") (pin "8") (pinfunction "8_8") (pintype "passive"))
    )
    (net (code "111") (name "Net-(U10B-O)") (class "Default")
      (node (ref "JP10") (pin "2") (pinfunction "2_2") (pintype "passive"))
      (node (ref "U10") (pin "5") (pinfunction "O_5") (pintype "output"))
      (node (ref "U9") (pin "1") (pinfunction "OUT_1") (pintype "output"))
      (node (ref "X7") (pin "7") (pinfunction "7_7") (pintype "passive"))
    )
    (net (code "112") (name "Net-(U11A-QA)") (class "Default")
      (node (ref "R59") (pin "1") (pinfunction "1_1") (pintype "passive"))
      (node (ref "U11") (pin "15") (pinfunction "QA_15") (pintype "tri_state"))
      (node (ref "U12") (pin "1") (pinfunction "I1_1") (pintype "input"))
    )
    (net (code "113") (name "Net-(U11A-QB)") (class "Default")
      (node (ref "R58") (pin "1") (pinfunction "1_1") (pintype "passive"))
      (node (ref "U11") (pin "1") (pinfunction "QB_1") (pintype "tri_state"))
      (node (ref "U12") (pin "2") (pinfunction "I2_2") (pintype "input"))
    )
    (net (code "114") (name "Net-(U11A-QC)") (class "Default")
      (node (ref "R57") (pin "1") (pinfunction "1_1") (pintype "passive"))
      (node (ref "U11") (pin "2") (pinfunction "QC_2") (pintype "tri_state"))
      (node (ref "U12") (pin "3") (pinfunction "I3_3") (pintype "input"))
    )
    (net (code "115") (name "Net-(U11A-QD)") (class "Default")
      (node (ref "R56") (pin "1") (pinfunction "1_1") (pintype "passive"))
      (node (ref "U11") (pin "3") (pinfunction "QD_3") (pintype "tri_state"))
      (node (ref "U12") (pin "4") (pinfunction "I4_4") (pintype "input"))
    )
    (net (code "116") (name "Net-(U11A-QE)") (class "Default")
      (node (ref "R55") (pin "1") (pinfunction "1_1") (pintype "passive"))
      (node (ref "U11") (pin "4") (pinfunction "QE_4") (pintype "tri_state"))
      (node (ref "U12") (pin "5") (pinfunction "I5_5") (pintype "input"))
    )
    (net (code "117") (name "Net-(U11A-QF)") (class "Default")
      (node (ref "R54") (pin "1") (pinfunction "1_1") (pintype "passive"))
      (node (ref "U11") (pin "5") (pinfunction "QF_5") (pintype "tri_state"))
      (node (ref "U12") (pin "6") (pinfunction "I6_6") (pintype "input"))
    )
    (net (code "118") (name "Net-(U11A-QG)") (class "Default")
      (node (ref "R53") (pin "1") (pinfunction "1_1") (pintype "passive"))
      (node (ref "U11") (pin "6") (pinfunction "QG_6") (pintype "tri_state"))
      (node (ref "U12") (pin "7") (pinfunction "I7_7") (pintype "input"))
    )
    (net (code "119") (name "Net-(U11A-QH)") (class "Default")
      (node (ref "R52") (pin "1") (pinfunction "1_1") (pintype "passive"))
      (node (ref "U11") (pin "7") (pinfunction "QH_7") (pintype "tri_state"))
      (node (ref "U12") (pin "8") (pinfunction "I8_8") (pintype "input"))
    )
    (net (code "120") (name "Net-(U13A-QA)") (class "Default")
      (node (ref "R67") (pin "1") (pinfunction "1_1") (pintype "passive"))
      (node (ref "U13") (pin "15") (pinfunction "QA_15") (pintype "tri_state"))
      (node (ref "U14") (pin "1") (pinfunction "I1_1") (pintype "input"))
    )
    (net (code "121") (name "Net-(U13A-QB)") (class "Default")
      (node (ref "R66") (pin "1") (pinfunction "1_1") (pintype "passive"))
      (node (ref "U13") (pin "1") (pinfunction "QB_1") (pintype "tri_state"))
      (node (ref "U14") (pin "2") (pinfunction "I2_2") (pintype "input"))
    )
    (net (code "122") (name "Net-(U13A-QC)") (class "Default")
      (node (ref "R65") (pin "1") (pinfunction "1_1") (pintype "passive"))
      (node (ref "U13") (pin "2") (pinfunction "QC_2") (pintype "tri_state"))
      (node (ref "U14") (pin "3") (pinfunction "I3_3") (pintype "input"))
    )
    (net (code "123") (name "Net-(U13A-QD)") (class "Default")
      (node (ref "R64") (pin "1") (pinfunction "1_1") (pintype "passive"))
      (node (ref "U13") (pin "3") (pinfunction "QD_3") (pintype "tri_state"))
      (node (ref "U14") (pin "4") (pinfunction "I4_4") (pintype "input"))
    )
    (net (code "124") (name "Net-(U13A-QE)") (class "Default")
      (node (ref "R63") (pin "1") (pinfunction "1_1") (pintype "passive"))
      (node (ref "U13") (pin "4") (pinfunction "QE_4") (pintype "tri_state"))
      (node (ref "U14") (pin "5") (pinfunction "I5_5") (pintype "input"))
    )
    (net (code "125") (name "Net-(U13A-QF)") (class "Default")
      (node (ref "R62") (pin "1") (pinfunction "1_1") (pintype "passive"))
      (node (ref "U13") (pin "5") (pinfunction "QF_5") (pintype "tri_state"))
      (node (ref "U14") (pin "6") (pinfunction "I6_6") (pintype "input"))
    )
    (net (code "126") (name "Net-(U13A-QG)") (class "Default")
      (node (ref "R61") (pin "1") (pinfunction "1_1") (pintype "passive"))
      (node (ref "U13") (pin "6") (pinfunction "QG_6") (pintype "tri_state"))
      (node (ref "U14") (pin "7") (pinfunction "I7_7") (pintype "input"))
    )
    (net (code "127") (name "Net-(U13A-QH)") (class "Default")
      (node (ref "R60") (pin "1") (pinfunction "1_1") (pintype "passive"))
      (node (ref "U13") (pin "7") (pinfunction "QH_7") (pintype "tri_state"))
      (node (ref "U14") (pin "8") (pinfunction "I8_8") (pintype "input"))
    )
    (net (code "128") (name "Net-(X1-Pad4)") (class "Default")
      (node (ref "X1") (pin "4") (pinfunction "4_4") (pintype "passive"))
      (node (ref "X2") (pin "4") (pinfunction "4_4") (pintype "passive"))
    )
    (net (code "129") (name "Net-(X1-Pad5)") (class "Default")
      (node (ref "X1") (pin "5") (pinfunction "5_5") (pintype "passive"))
      (node (ref "X2") (pin "5") (pinfunction "5_5") (pintype "passive"))
    )
    (net (code "130") (name "OLAT") (class "Default")
      (node (ref "G1") (pin "PA8") (pinfunction "PA8_PA8") (pintype "bidirectional"))
      (node (ref "R3") (pin "1") (pinfunction "1_1") (pintype "passive"))
      (node (ref "U11") (pin "12") (pinfunction "RCK_12") (pintype "input"))
      (node (ref "U13") (pin "12") (pinfunction "RCK_12") (pintype "input"))
    )
    (net (code "131") (name "SCK") (class "Default")
      (node (ref "G1") (pin "PB3") (pinfunction "PB3_PB3") (pintype "bidirectional"))
      (node (ref "JP5") (pin "3") (pinfunction "3_3") (pintype "passive"))
      (node (ref "R5") (pin "1") (pinfunction "1_1") (pintype "passive"))
      (node (ref "U11") (pin "11") (pinfunction "SCK_11") (pintype "input"))
      (node (ref "U13") (pin "11") (pinfunction "SCK_11") (pintype "input"))
    )
    (net (code "132") (name "SCK2") (class "Default")
      (node (ref "G1") (pin "PB10") (pinfunction "PB10_PB10") (pintype "bidirectional"))
      (node (ref "SJ2") (pin "P$1") (pinfunction "1_P$1") (pintype "passive"))
      (node (ref "U3") (pin "7") (pinfunction "CLK_7") (pintype "input"))
      (node (ref "U4") (pin "7") (pinfunction "CLK_7") (pintype "input"))
    )
    (net (code "133") (name "SLNK1") (class "Default")
      (node (ref "SJ14") (pin "P$1") (pinfunction "1_P$1") (pintype "passive"))
      (node (ref "U11") (pin "14") (pinfunction "SER_14") (pintype "input"))
      (node (ref "U13") (pin "9") (pinfunction "QH*_9") (pintype "tri_state"))
    )
    (net (code "134") (name "SLNK2") (class "Default")
      (node (ref "SJ5") (pin "P$1") (pinfunction "1_P$1") (pintype "passive"))
      (node (ref "U11") (pin "9") (pinfunction "QH*_9") (pintype "tri_state"))
    )
    (net (code "135") (name "SLNK3") (class "Default")
      (node (ref "SJ7") (pin "P$1") (pinfunction "1_P$1") (pintype "passive"))
      (node (ref "U3") (pin "1") (pinfunction "SER_1") (pintype "input"))
      (node (ref "U4") (pin "13") (pinfunction "QH_13") (pintype "output"))
    )
    (net (code "136") (name "SRV1") (class "Default")
      (node (ref "G1") (pin "PC9") (pinfunction "PC9_PC9") (pintype "bidirectional"))
      (node (ref "JP4") (pin "2") (pinfunction "2_2") (pintype "passive"))
      (node (ref "R13") (pin "2") (pinfunction "2_2") (pintype "passive"))
    )
    (net (code "137") (name "SRV2") (class "Default")
      (node (ref "G1") (pin "PC7") (pinfunction "PC7_PC7") (pintype "bidirectional"))
      (node (ref "JP4") (pin "1") (pinfunction "1_1") (pintype "passive"))
      (node (ref "R12") (pin "2") (pinfunction "2_2") (pintype "passive"))
    )
    (net (code "138") (name "SRV3") (class "Default")
      (node (ref "G1") (pin "PC8") (pinfunction "PC8_PC8") (pintype "bidirectional"))
      (node (ref "JP3") (pin "2") (pinfunction "2_2") (pintype "passive"))
      (node (ref "R11") (pin "2") (pinfunction "2_2") (pintype "passive"))
    )
    (net (code "139") (name "SRV4") (class "Default")
      (node (ref "G1") (pin "PC6") (pinfunction "PC6_PC6") (pintype "bidirectional"))
      (node (ref "JP3") (pin "1") (pinfunction "1_1") (pintype "passive"))
      (node (ref "R10") (pin "2") (pinfunction "2_2") (pintype "passive"))
    )
    (net (code "140") (name "SRV5") (class "Default")
      (node (ref "G1") (pin "PC12") (pinfunction "PC12_PC12") (pintype "bidirectional"))
      (node (ref "JP2") (pin "2") (pinfunction "2_2") (pintype "passive"))
      (node (ref "R9") (pin "2") (pinfunction "2_2") (pintype "passive"))
    )
    (net (code "141") (name "SRV6") (class "Default")
      (node (ref "G1") (pin "PA15") (pinfunction "PA15_PA15") (pintype "bidirectional"))
      (node (ref "JP2") (pin "1") (pinfunction "1_1") (pintype "passive"))
      (node (ref "R8") (pin "2") (pinfunction "2_2") (pintype "passive"))
    )
    (net (code "142") (name "SRV7") (class "Default")
      (node (ref "G1") (pin "PF1-PH1") (pinfunction "PF1-PH1_PF1-PH1") (pintype "bidirectional"))
      (node (ref "JP1") (pin "2") (pinfunction "2_2") (pintype "passive"))
      (node (ref "R7") (pin "2") (pinfunction "2_2") (pintype "passive"))
    )
    (net (code "143") (name "SRV8") (class "Default")
      (node (ref "G1") (pin "PD2") (pinfunction "PD2_PD2") (pintype "bidirectional"))
      (node (ref "JP1") (pin "1") (pinfunction "1_1") (pintype "passive"))
      (node (ref "R6") (pin "2") (pinfunction "2_2") (pintype "passive"))
    )
    (net (code "144") (name "TDRV1") (class "Default")
      (node (ref "G1") (pin "PB12") (pinfunction "PB12_PB12") (pintype "bidirectional"))
      (node (ref "U10") (pin "2") (pinfunction "I_2") (pintype "input"))
      (node (ref "U9") (pin "12") (pinfunction "+IN_12") (pintype "input"))
    )
    (net (code "145") (name "TDRV2") (class "Default")
      (node (ref "G1") (pin "PB2") (pinfunction "PB2_PB2") (pintype "bidirectional"))
      (node (ref "U10") (pin "4") (pinfunction "I_4") (pintype "input"))
      (node (ref "U9") (pin "3") (pinfunction "+IN_3") (pintype "input"))
    )
    (net (code "146") (name "TDRV3") (class "Default")
      (node (ref "G1") (pin "PB15") (pinfunction "PB15_PB15") (pintype "bidirectional"))
      (node (ref "U8") (pin "4") (pinfunction "I_4") (pintype "input"))
      (node (ref "U9") (pin "10") (pinfunction "+IN_10") (pintype "input"))
    )
    (net (code "147") (name "TDRV4") (class "Default")
      (node (ref "G1") (pin "PB1") (pinfunction "PB1_PB1") (pintype "bidirectional"))
      (node (ref "U8") (pin "2") (pinfunction "I_2") (pintype "input"))
      (node (ref "U9") (pin "5") (pinfunction "+IN_5") (pintype "input"))
    )
    (net (code "148") (name "TDRV5") (class "Default")
      (node (ref "G1") (pin "PA0") (pinfunction "PA0_PA0") (pintype "bidirectional"))
      (node (ref "U6") (pin "12") (pinfunction "+IN_12") (pintype "input"))
      (node (ref "U7") (pin "2") (pinfunction "I_2") (pintype "input"))
    )
    (net (code "149") (name "TDRV6") (class "Default")
      (node (ref "G1") (pin "PA4") (pinfunction "PA4_PA4") (pintype "bidirectional"))
      (node (ref "U6") (pin "3") (pinfunction "+IN_3") (pintype "input"))
      (node (ref "U7") (pin "4") (pinfunction "I_4") (pintype "input"))
    )
    (net (code "150") (name "TDRV7") (class "Default")
      (node (ref "G1") (pin "PC3") (pinfunction "PC3_PC3") (pintype "bidirectional"))
      (node (ref "U5") (pin "4") (pinfunction "I_4") (pintype "input"))
      (node (ref "U6") (pin "10") (pinfunction "+IN_10") (pintype "input"))
    )
    (net (code "151") (name "TDRV8") (class "Default")
      (node (ref "G1") (pin "PC0") (pinfunction "PC0_PC0") (pintype "bidirectional"))
      (node (ref "U5") (pin "2") (pinfunction "I_2") (pintype "input"))
      (node (ref "U6") (pin "5") (pinfunction "+IN_5") (pintype "input"))
    )
    (net (code "152") (name "V+") (class "Default")
      (node (ref "C6") (pin "+") (pinfunction "+_+") (pintype "passive"))
      (node (ref "C7") (pin "1") (pinfunction "1_1") (pintype "passive"))
      (node (ref "G1") (pin "E5V") (pinfunction "E5V_E5V") (pintype "power_in"))
      (node (ref "L1") (pin "1") (pinfunction "1_1") (pintype "passive"))
      (node (ref "U2") (pin "3") (pinfunction "FB_3") (pintype "bidirectional"))
      (node (ref "U2B") (pin "1") (pinfunction "FB_1") (pintype "input"))
    )
    (net (code "153") (name "unconnected-(G1-PadBOOT0)") (class "Default")
      (node (ref "G1") (pin "BOOT0") (pinfunction "BOOT0_BOOT0") (pintype "bidirectional"))
    )
    (net (code "154") (name "unconnected-(G1-PadIOREF2)") (class "Default")
      (node (ref "G1") (pin "IOREF2") (pinfunction "IOREF2_IOREF2") (pintype "input"))
    )
    (net (code "155") (name "unconnected-(G1-PadNC1-PF7)") (class "Default")
      (node (ref "G1") (pin "NC1-PF7") (pinfunction "NC1-PF7_NC1-PF7") (pintype "bidirectional"))
    )
    (net (code "156") (name "unconnected-(G1-PadNC2-PF6)") (class "Default")
      (node (ref "G1") (pin "NC2-PF6") (pinfunction "NC2-PF6_NC2-PF6") (pintype "bidirectional"))
    )
    (net (code "157") (name "unconnected-(G1-PadNC3)") (class "Default")
      (node (ref "G1") (pin "NC3") (pinfunction "NC3_NC3") (pintype "no_connect"))
    )
    (net (code "158") (name "unconnected-(G1-PadNC4)") (class "Default")
      (node (ref "G1") (pin "NC4") (pinfunction "NC4_NC4") (pintype "no_connect"))
    )
    (net (code "159") (name "unconnected-(G1-PadNC5-PD8)") (class "Default")
      (node (ref "G1") (pin "NC5-PD8") (pinfunction "NC5-PD8_NC5-PD8") (pintype "bidirectional"))
    )
    (net (code "160") (name "unconnected-(G1-PadNC6-PB11)") (class "Default")
      (node (ref "G1") (pin "NC6-PB11") (pinfunction "NC6-PB11_NC6-PB11") (pintype "no_connect"))
    )
    (net (code "161") (name "unconnected-(G1-PadNC7-PF5)") (class "Default")
      (node (ref "G1") (pin "NC7-PF5") (pinfunction "NC7-PF5_NC7-PF5") (pintype "bidirectional"))
    )
    (net (code "162") (name "unconnected-(G1-PadNC8-PF4)") (class "Default")
      (node (ref "G1") (pin "NC8-PF4") (pinfunction "NC8-PF4_NC8-PF4") (pintype "bidirectional"))
    )
    (net (code "163") (name "unconnected-(G1-PadNRESET)") (class "Default")
      (node (ref "G1") (pin "NRESET") (pinfunction "NRESET_NRESET") (pintype "input"))
    )
    (net (code "164") (name "unconnected-(G1-PadPA1)") (class "Default")
      (node (ref "G1") (pin "PA1") (pinfunction "PA1_PA1") (pintype "bidirectional"))
    )
    (net (code "165") (name "unconnected-(G1-PadPA2)") (class "Default")
      (node (ref "G1") (pin "PA2") (pinfunction "PA2_PA2") (pintype "bidirectional"))
    )
    (net (code "166") (name "unconnected-(G1-PadPA3)") (class "Default")
      (node (ref "G1") (pin "PA3") (pinfunction "PA3_PA3") (pintype "bidirectional"))
    )
    (net (code "167") (name "unconnected-(G1-PadPA5)") (class "Default")
      (node (ref "G1") (pin "PA5") (pinfunction "PA5_PA5") (pintype "bidirectional"))
    )
    (net (code "168") (name "unconnected-(G1-PadPA7)") (class "Default")
      (node (ref "G1") (pin "PA7") (pinfunction "PA7_PA7") (pintype "bidirectional"))
    )
    (net (code "169") (name "unconnected-(G1-PadPA9)") (class "Default")
      (node (ref "G1") (pin "PA9") (pinfunction "PA9_PA9") (pintype "bidirectional"))
    )
    (net (code "170") (name "unconnected-(G1-PadPA10)") (class "Default")
      (node (ref "G1") (pin "PA10") (pinfunction "PA10_PA10") (pintype "bidirectional"))
    )
    (net (code "171") (name "unconnected-(G1-PadPA11)") (class "Default")
      (node (ref "G1") (pin "PA11") (pinfunction "PA11_PA11") (pintype "bidirectional"))
    )
    (net (code "172") (name "unconnected-(G1-PadPA12)") (class "Default")
      (node (ref "G1") (pin "PA12") (pinfunction "PA12_PA12") (pintype "bidirectional"))
    )
    (net (code "173") (name "unconnected-(G1-PadPA13)") (class "Default")
      (node (ref "G1") (pin "PA13") (pinfunction "PA13_PA13") (pintype "bidirectional"))
    )
    (net (code "174") (name "unconnected-(G1-PadPA14)") (class "Default")
      (node (ref "G1") (pin "PA14") (pinfunction "PA14_PA14") (pintype "bidirectional"))
    )
    (net (code "175") (name "unconnected-(G1-PadPB0)") (class "Default")
      (node (ref "G1") (pin "PB0") (pinfunction "PB0_PB0") (pintype "bidirectional"))
    )
    (net (code "176") (name "unconnected-(G1-PadPC1)") (class "Default")
      (node (ref "G1") (pin "PC1") (pinfunction "PC1_PC1") (pintype "bidirectional"))
    )
    (net (code "177") (name "unconnected-(G1-PadPC4)") (class "Default")
      (node (ref "G1") (pin "PC4") (pinfunction "PC4_PC4") (pintype "bidirectional"))
    )
    (net (code "178") (name "unconnected-(G1-PadPC5)") (class "Default")
      (node (ref "G1") (pin "PC5") (pinfunction "PC5_PC5") (pintype "bidirectional"))
    )
    (net (code "179") (name "unconnected-(G1-PadPC13)") (class "Default")
      (node (ref "G1") (pin "PC13") (pinfunction "PC13_PC13") (pintype "bidirectional"))
    )
    (net (code "180") (name "unconnected-(G1-PadPC14)") (class "Default")
      (node (ref "G1") (pin "PC14") (pinfunction "PC14_PC14") (pintype "bidirectional"))
    )
    (net (code "181") (name "unconnected-(G1-PadPC15)") (class "Default")
      (node (ref "G1") (pin "PC15") (pinfunction "PC15_PC15") (pintype "bidirectional"))
    )
    (net (code "182") (name "unconnected-(G1-PadPF0-PH0)") (class "Default")
      (node (ref "G1") (pin "PF0-PH0") (pinfunction "PF0-PH0_PF0-PH0") (pintype "bidirectional"))
    )
    (net (code "183") (name "unconnected-(H1-MOUNT-PadB3,3)") (class "Default")
      (node (ref "H1") (pin "B3,3") (pinfunction "MOUNT_B3,3") (pintype "passive"))
    )
    (net (code "184") (name "unconnected-(H2-MOUNT-PadB3,3)") (class "Default")
      (node (ref "H2") (pin "B3,3") (pinfunction "MOUNT_B3,3") (pintype "passive"))
    )
    (net (code "185") (name "unconnected-(H3-MOUNT-PadB3,3)") (class "Default")
      (node (ref "H3") (pin "B3,3") (pinfunction "MOUNT_B3,3") (pintype "passive"))
    )
    (net (code "186") (name "unconnected-(H4-MOUNT-PadB3,3)") (class "Default")
      (node (ref "H4") (pin "B3,3") (pinfunction "MOUNT_B3,3") (pintype "passive"))
    )
  )
)
